# VFD-Clock.net
KiCad netlist of a schematic drawn in Altium Designer
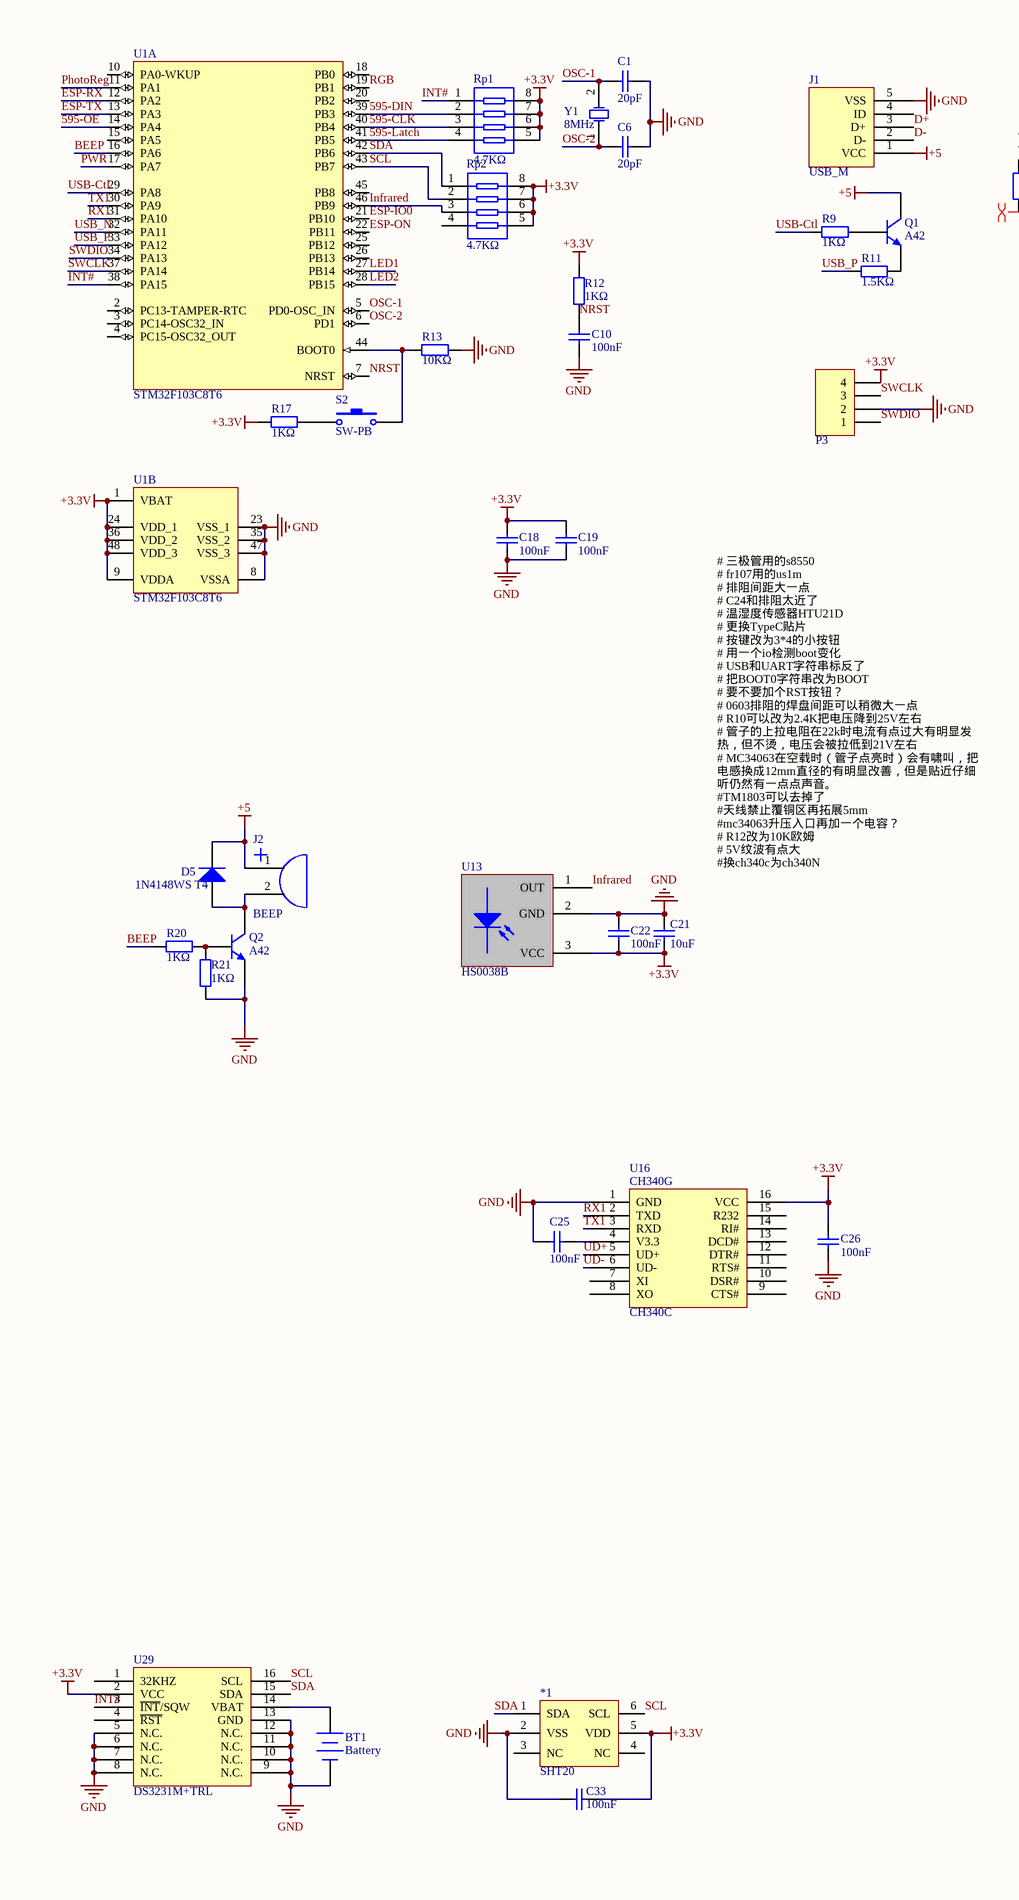
[diagram p0: VFD-Clock.SchDoc, left]
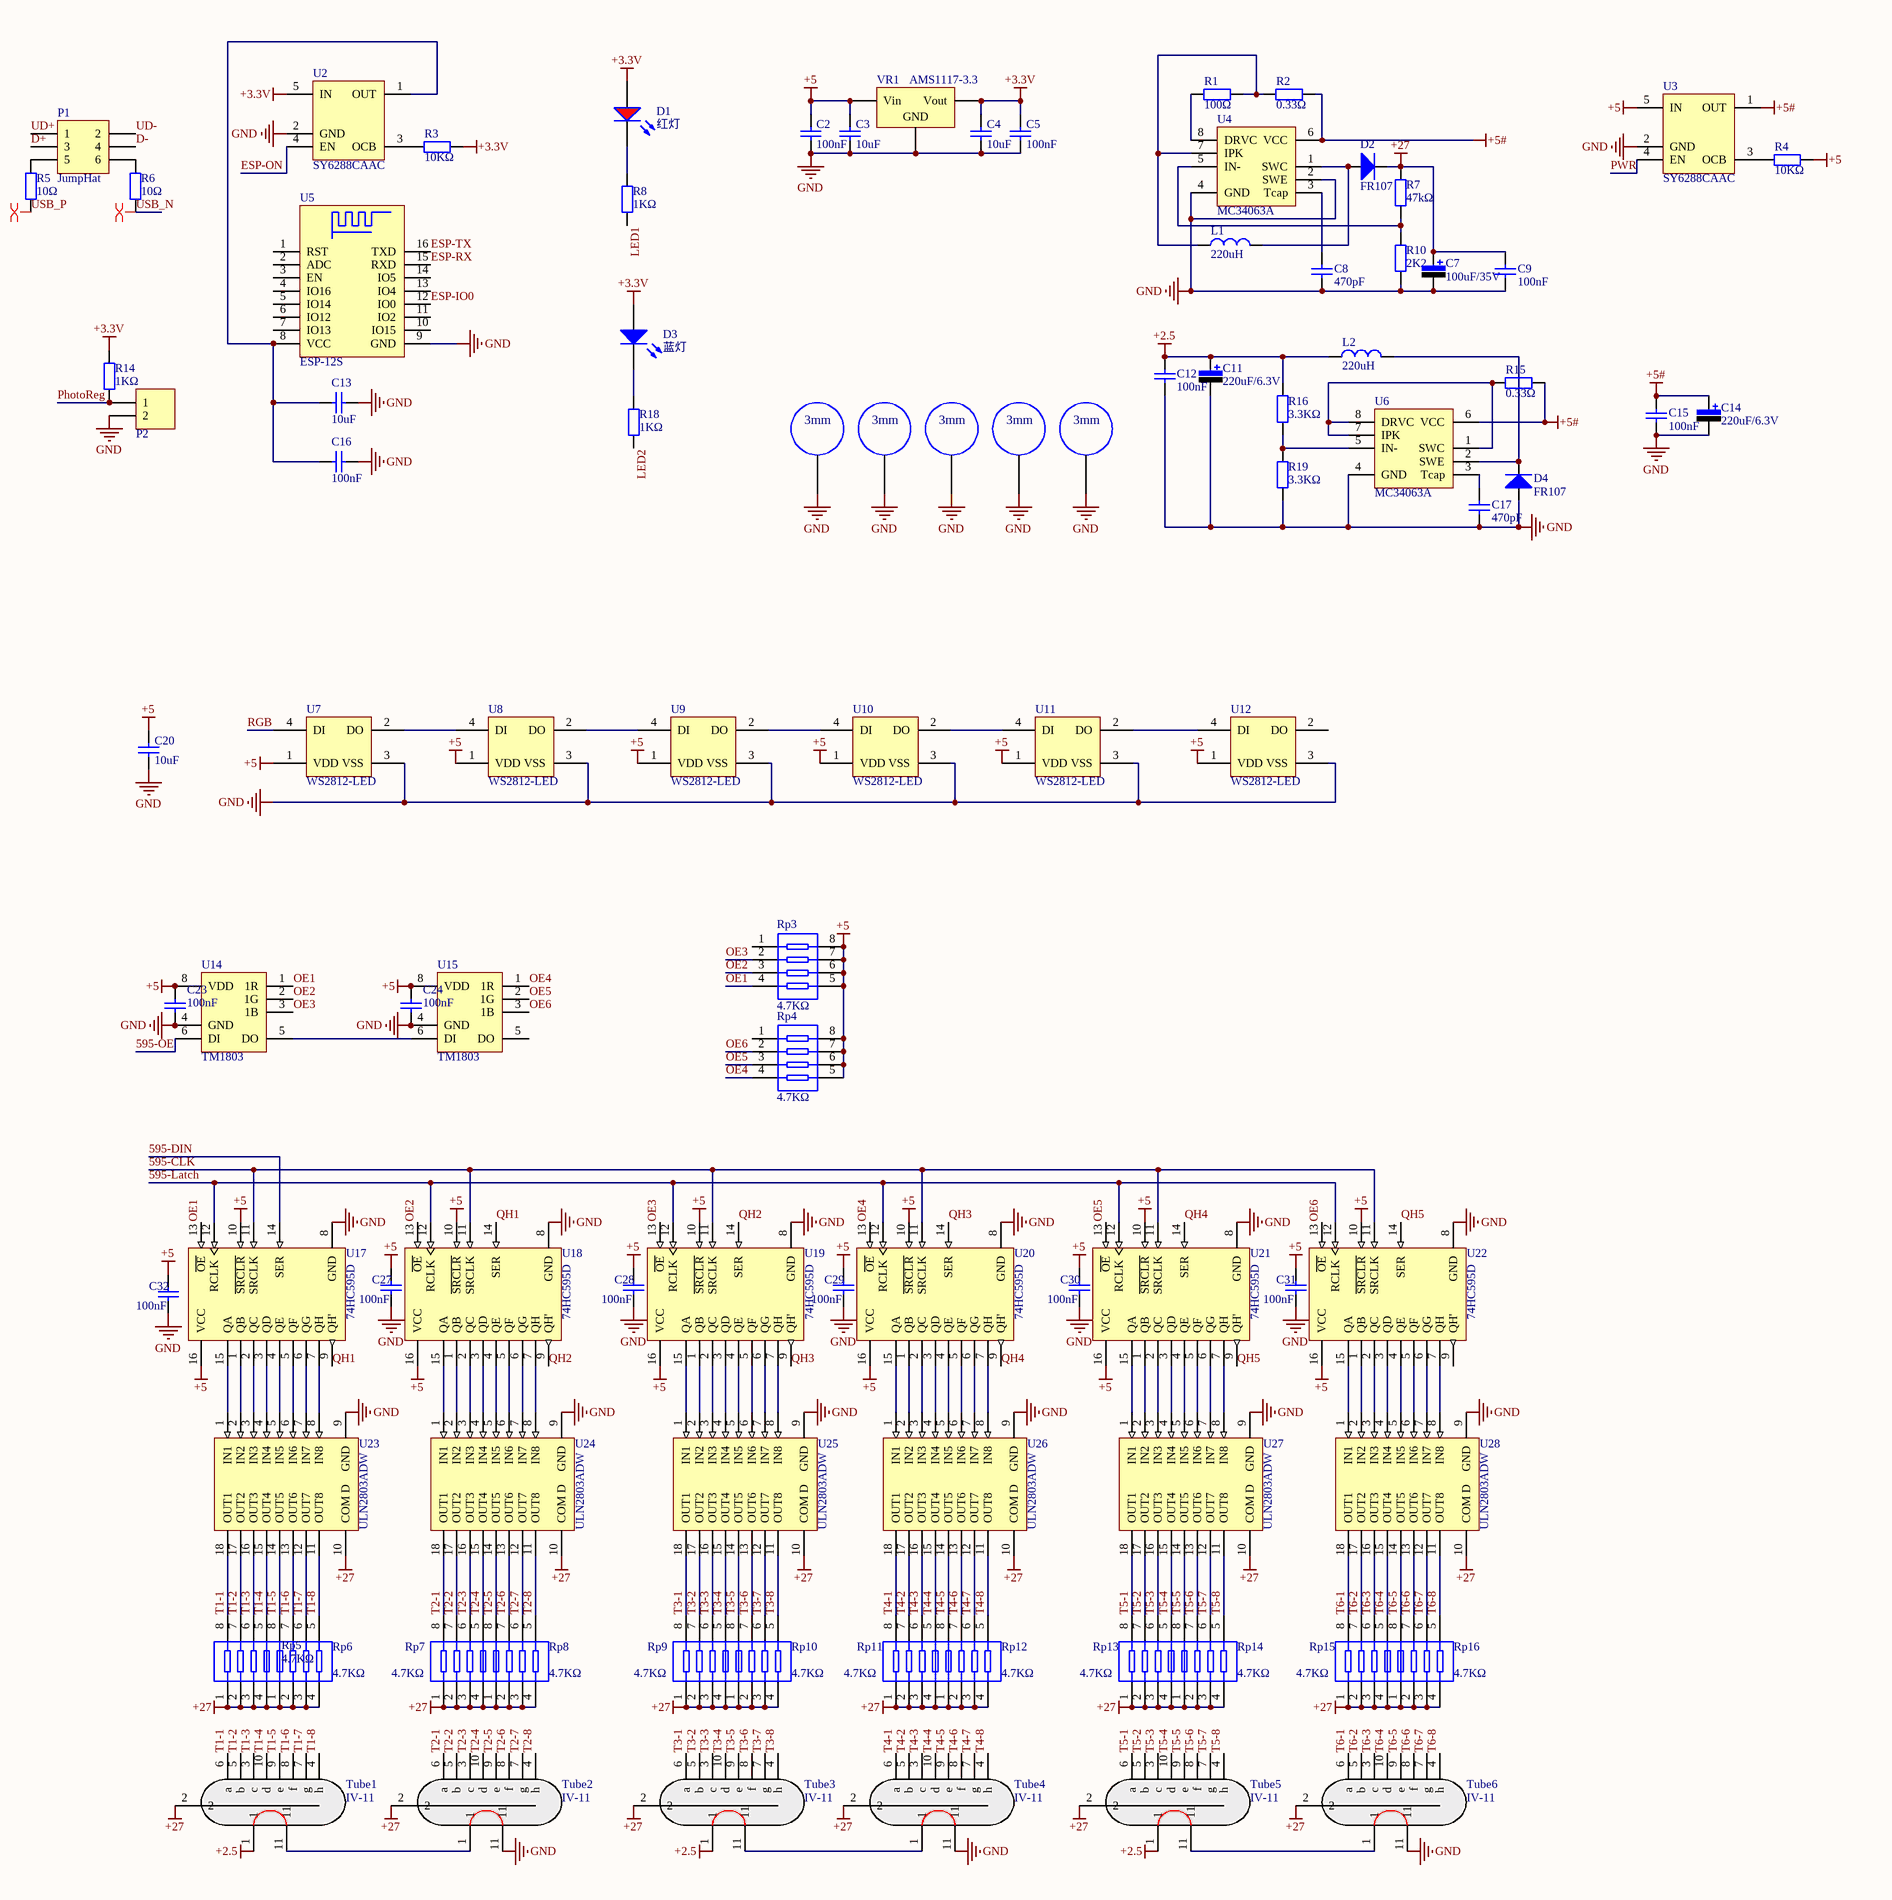
[diagram p1: VFD-Clock.SchDoc, right]

(export (version "E")
  (design (tool "Eeschema 10.0.6"))
  (components
    (comp (ref "*1")
      (value "SHT20")
      (footprint "DFN6")
      (description "温湿度传感器")
      (libsource (lib "fszhang") (part "SHT20"))
    )
    (comp (ref "BT1")
      (value "Battery")
      (footprint "CR1220")
      (description "备份电池")
      (fields (field (name "PUBLISHER") "Altium Limited"))
      (libsource (lib "fszhang") (part "Battery"))
    )
    (comp (ref "C1")
      (value "20pF")
      (footprint "0805_C")
      (description "贴片电容")
      (libsource (lib "Miscellaneous Devices LC") (part "0805 20pF (200) 5% 50V"))
    )
    (comp (ref "C2")
      (value "100nF")
      (footprint "0805_C")
      (description "贴片电容")
      (libsource (lib "Miscellaneous Devices LC") (part "0805 100nF(104) 10% 50V"))
    )
    (comp (ref "C3")
      (value "10uF")
      (footprint "0805_C")
      (description "贴片电容")
      (libsource (lib "Miscellaneous Devices LC") (part "0805 10uF (106) 10% 25V"))
    )
    (comp (ref "C4")
      (value "10uF")
      (footprint "0805_C")
      (description "贴片电容")
      (libsource (lib "Miscellaneous Devices LC") (part "0805 10uF (106) 10% 25V"))
    )
    (comp (ref "C5")
      (value "100nF")
      (footprint "0805_C")
      (description "贴片电容")
      (libsource (lib "Miscellaneous Devices LC") (part "0805 100nF(104) 10% 50V"))
    )
    (comp (ref "C6")
      (value "20pF")
      (footprint "0805_C")
      (description "贴片电容")
      (libsource (lib "Miscellaneous Devices LC") (part "0805 20pF (200) 5% 50V"))
    )
    (comp (ref "C7")
      (value "100uF/35V")
      (footprint "CAP-7343")
      (description "极性电解电容")
      (fields (field (name "PUBLISHER") "Altium Limited"))
      (libsource (lib "fszhang") (part "Cap Pol"))
    )
    (comp (ref "C8")
      (value "470pF")
      (footprint "0805_C")
      (description "贴片电容")
      (libsource (lib "Miscellaneous Devices LC") (part "0805 470pF (471) 10% 50V"))
    )
    (comp (ref "C9")
      (value "100nF")
      (footprint "0805_C")
      (description "贴片电容")
      (libsource (lib "Miscellaneous Devices LC") (part "0805 100nF(104) 10% 50V"))
    )
    (comp (ref "C10")
      (value "100nF")
      (footprint "0805_C")
      (description "贴片电容")
      (libsource (lib "Miscellaneous Devices LC") (part "0805 100nF(104) 10% 50V"))
    )
    (comp (ref "C11")
      (value "220uF/6.3V")
      (footprint "CAP-3528")
      (description "极性电解电容")
      (fields (field (name "PUBLISHER") "Altium Limited"))
      (libsource (lib "fszhang") (part "Cap Pol"))
    )
    (comp (ref "C12")
      (value "100nF")
      (footprint "0805_C")
      (description "贴片电容")
      (libsource (lib "Miscellaneous Devices LC") (part "0805 100nF(104) 10% 50V"))
    )
    (comp (ref "C13")
      (value "10uF")
      (footprint "0805_C")
      (description "贴片电容")
      (libsource (lib "Miscellaneous Devices LC") (part "0805 10uF (106) 10% 25V"))
    )
    (comp (ref "C14")
      (value "220uF/6.3V")
      (footprint "CAP-3528")
      (description "极性电解电容")
      (fields (field (name "PUBLISHER") "Altium Limited"))
      (libsource (lib "fszhang") (part "Cap Pol"))
    )
    (comp (ref "C15")
      (value "100nF")
      (footprint "0805_C")
      (description "贴片电容")
      (libsource (lib "Miscellaneous Devices LC") (part "0805 100nF(104) 10% 50V"))
    )
    (comp (ref "C16")
      (value "100nF")
      (footprint "0805_C")
      (description "贴片电容")
      (libsource (lib "Miscellaneous Devices LC") (part "0805 100nF(104) 10% 50V"))
    )
    (comp (ref "C17")
      (value "470pF")
      (footprint "0805_C")
      (description "贴片电容")
      (libsource (lib "Miscellaneous Devices LC") (part "0805 470pF (471) 10% 50V"))
    )
    (comp (ref "C18")
      (value "100nF")
      (footprint "0805_C")
      (description "贴片电容")
      (libsource (lib "Miscellaneous Devices LC") (part "0805 100nF(104) 10% 50V"))
    )
    (comp (ref "C19")
      (value "100nF")
      (footprint "0805_C")
      (description "贴片电容")
      (libsource (lib "Miscellaneous Devices LC") (part "0805 100nF(104) 10% 50V"))
    )
    (comp (ref "C20")
      (value "10uF")
      (footprint "0805_C")
      (description "贴片电容")
      (libsource (lib "Miscellaneous Devices LC") (part "0805 10uF (106) 10% 25V"))
    )
    (comp (ref "C21")
      (value "10uF")
      (footprint "0805_C")
      (description "贴片电容")
      (libsource (lib "Miscellaneous Devices LC") (part "0805 10uF (106) 10% 25V"))
    )
    (comp (ref "C22")
      (value "100nF")
      (footprint "0805_C")
      (description "贴片电容")
      (libsource (lib "Miscellaneous Devices LC") (part "0805 100nF(104) 10% 50V"))
    )
    (comp (ref "C23")
      (value "100nF")
      (footprint "0805_C")
      (description "贴片电容")
      (libsource (lib "Miscellaneous Devices LC") (part "0805 100nF(104) 10% 50V"))
    )
    (comp (ref "C24")
      (value "100nF")
      (footprint "0805_C")
      (description "贴片电容")
      (libsource (lib "Miscellaneous Devices LC") (part "0805 100nF(104) 10% 50V"))
    )
    (comp (ref "C25")
      (value "100nF")
      (footprint "0805_C")
      (description "贴片电容")
      (libsource (lib "Miscellaneous Devices LC") (part "0805 100nF(104) 10% 50V"))
    )
    (comp (ref "C26")
      (value "100nF")
      (footprint "0805_C")
      (description "贴片电容")
      (libsource (lib "Miscellaneous Devices LC") (part "0805 100nF(104) 10% 50V"))
    )
    (comp (ref "C27")
      (value "100nF")
      (footprint "0805_C")
      (description "贴片电容")
      (libsource (lib "Miscellaneous Devices LC") (part "0805 100nF(104) 10% 50V"))
    )
    (comp (ref "C28")
      (value "100nF")
      (footprint "0805_C")
      (description "贴片电容")
      (libsource (lib "Miscellaneous Devices LC") (part "0805 100nF(104) 10% 50V"))
    )
    (comp (ref "C29")
      (value "100nF")
      (footprint "0805_C")
      (description "贴片电容")
      (libsource (lib "Miscellaneous Devices LC") (part "0805 100nF(104) 10% 50V"))
    )
    (comp (ref "C30")
      (value "100nF")
      (footprint "0805_C")
      (description "贴片电容")
      (libsource (lib "Miscellaneous Devices LC") (part "0805 100nF(104) 10% 50V"))
    )
    (comp (ref "C31")
      (value "100nF")
      (footprint "0805_C")
      (description "贴片电容")
      (libsource (lib "Miscellaneous Devices LC") (part "0805 100nF(104) 10% 50V"))
    )
    (comp (ref "C32")
      (value "100nF")
      (footprint "0805_C")
      (description "贴片电容")
      (libsource (lib "Miscellaneous Devices LC") (part "0805 100nF(104) 10% 50V"))
    )
    (comp (ref "C33")
      (value "100nF")
      (footprint "0805_C")
      (description "贴片电容")
      (libsource (lib "Miscellaneous Devices LC") (part "0805 100nF(104) 10% 50V"))
    )
    (comp (ref "D1")
      (value "红灯")
      (footprint "0805_LED_S1")
      (description "发光二极管")
      (libsource (lib "Miscellaneous Devices LC") (part "0805 红灯"))
    )
    (comp (ref "D2")
      (value "FR107")
      (footprint "DIODE-SMA")
      (description "二极管")
      (fields (field (name "PUBLISHER") "Altium Limited"))
      (libsource (lib "fszhang") (part "Diode"))
    )
    (comp (ref "D3")
      (value "蓝灯")
      (footprint "0805_LED_S1")
      (description "发光二极管")
      (libsource (lib "Miscellaneous Devices LC") (part "0805 蓝灯"))
    )
    (comp (ref "D4")
      (value "FR107")
      (footprint "DIODE-SMA")
      (description "二极管")
      (fields (field (name "PUBLISHER") "Altium Limited"))
      (libsource (lib "fszhang") (part "Diode"))
    )
    (comp (ref "D5")
      (value "1N4148WS T4")
      (footprint "SOD-323")
      (description "二极管")
      (libsource (lib "Miscellaneous Devices LC") (part "SOD-323 1N4148WS T4"))
    )
    (comp (ref "J1")
      (value "USB_M")
      (footprint "USB_Micro2")
      (description "MicroUSB接口")
      (libsource (lib "fszhang") (part "USB_M"))
    )
    (comp (ref "J2")
      (value "BEEP")
      (footprint "BEEP-SMD-8530-3V-2.7KHZ")
      (description "蜂鸣器")
      (libsource (lib "fszhang") (part "BEEP"))
    )
    (comp (ref "L1")
      (value "220uH")
      (footprint "CDRH104R")
      (description "电感")
      (fields (field (name "PUBLISHER") "Altium Limited"))
      (libsource (lib "fszhang") (part "Inductor"))
    )
    (comp (ref "L2")
      (value "220uH")
      (footprint "CDRH104R")
      (description "电感")
      (fields (field (name "PUBLISHER") "Altium Limited"))
      (libsource (lib "fszhang") (part "Inductor"))
    )
    (comp (ref "P1")
      (value "JumpHat")
      (footprint "HDR2X3")
      (description "Header, 3-Pin, Dual row")
      (fields (field (name "PUBLISHER") "Altium Limited"))
      (libsource (lib "Miscellaneous Connectors") (part "Header 3X2"))
    )
    (comp (ref "P2")
      (value "Light Resister")
      (footprint "HDR2X1_A")
      (description "光敏电阻")
      (fields (field (name "PUBLISHER") "Altium Limited"))
      (libsource (lib "fszhang") (part "Header 2"))
    )
    (comp (ref "P3")
      (value "Header 4")
      (footprint "HDR4X1_A")
      (description "接插件")
      (fields (field (name "PUBLISHER") "Altium Limited"))
      (libsource (lib "fszhang") (part "Header 4"))
    )
    (comp (ref "Q1")
      (value "A42")
      (footprint "Miscellaneous Devices LC:SOT-23(SOT-23-3)")
      (description "三极管")
      (libsource (lib "Miscellaneous Devices LC") (part "SOT-23 SS8050 Y1"))
    )
    (comp (ref "Q2")
      (value "A42")
      (footprint "Miscellaneous Devices LC:SOT-23(SOT-23-3)")
      (description "三极管")
      (libsource (lib "Miscellaneous Devices LC") (part "SOT-23 SS8050 Y1"))
    )
    (comp (ref "R1")
      (value "100Ω")
      (footprint "0805_R")
      (description "贴片电阻")
      (libsource (lib "Miscellaneous Devices LC") (part "0805 100Ω (1000) 1%"))
    )
    (comp (ref "R2")
      (value "0.33Ω")
      (footprint "0805_R")
      (description "贴片电阻")
      (libsource (lib "Miscellaneous Devices LC") (part "0805 100Ω (1000) 1%"))
    )
    (comp (ref "R3")
      (value "10KΩ")
      (footprint "0805_R")
      (description "贴片电阻")
      (libsource (lib "Miscellaneous Devices LC") (part "0805 10KΩ (1002) 1%"))
    )
    (comp (ref "R4")
      (value "10KΩ")
      (footprint "0805_R")
      (description "贴片电阻")
      (libsource (lib "Miscellaneous Devices LC") (part "0805 10KΩ (1002) 1%"))
    )
    (comp (ref "R5")
      (value "10Ω")
      (footprint "0805_R")
      (description "贴片电阻")
      (libsource (lib "Miscellaneous Devices LC") (part "0805 10Ω (10R0) 1%"))
    )
    (comp (ref "R6")
      (value "10Ω")
      (footprint "0805_R")
      (description "贴片电阻")
      (libsource (lib "") (part "0805 10Ω (10R0) 1%_1"))
    )
    (comp (ref "R7")
      (value "47kΩ")
      (footprint "0805_R")
      (description "贴片电阻")
      (libsource (lib "") (part "0805 100Ω (1000) 1%_1"))
    )
    (comp (ref "R8")
      (value "1KΩ")
      (footprint "0805_R")
      (description "贴片电阻")
      (libsource (lib "") (part "0805 1KΩ (1001) 1%_3"))
    )
    (comp (ref "R9")
      (value "1KΩ")
      (footprint "0805_R")
      (description "贴片电阻")
      (libsource (lib "") (part "0805 1KΩ (1001) 1%_1"))
    )
    (comp (ref "R10")
      (value "2K2")
      (footprint "0805_R")
      (description "贴片电阻")
      (libsource (lib "") (part "0805 100Ω (1000) 1%_1"))
    )
    (comp (ref "R11")
      (value "1.5KΩ")
      (footprint "0805_R")
      (description "贴片电阻")
      (libsource (lib "Miscellaneous Devices LC") (part "0805 1.5KΩ (1501) 1%"))
    )
    (comp (ref "R12")
      (value "1KΩ")
      (footprint "0805_R")
      (description "贴片电阻")
      (libsource (lib "Miscellaneous Devices LC") (part "0805 1KΩ (1001) 1%"))
    )
    (comp (ref "R13")
      (value "10KΩ")
      (footprint "0805_R")
      (description "贴片电阻")
      (libsource (lib "") (part "0805 10KΩ (1002) 1%_1"))
    )
    (comp (ref "R14")
      (value "1KΩ")
      (footprint "0805_R")
      (description "贴片电阻")
      (libsource (lib "Miscellaneous Devices LC") (part "0805 1KΩ (1001) 1%"))
    )
    (comp (ref "R15")
      (value "0.33Ω")
      (footprint "0805_R")
      (description "贴片电阻")
      (libsource (lib "Miscellaneous Devices LC") (part "0805 100Ω (1000) 1%"))
    )
    (comp (ref "R16")
      (value "3.3KΩ")
      (footprint "0805_R")
      (description "贴片电阻")
      (libsource (lib "Miscellaneous Devices LC") (part "0805 3.3KΩ (3301) 1%"))
    )
    (comp (ref "R17")
      (value "1KΩ")
      (footprint "0805_R")
      (description "贴片电阻")
      (libsource (lib "") (part "0805 1KΩ (1001) 1%_2"))
    )
    (comp (ref "R18")
      (value "1KΩ")
      (footprint "0805_R")
      (description "贴片电阻")
      (libsource (lib "") (part "0805 1KΩ (1001) 1%_3"))
    )
    (comp (ref "R19")
      (value "3.3KΩ")
      (footprint "0805_R")
      (description "贴片电阻")
      (libsource (lib "Miscellaneous Devices LC") (part "0805 3.3KΩ (3301) 1%"))
    )
    (comp (ref "R20")
      (value "1KΩ")
      (footprint "0805_R")
      (description "贴片电阻")
      (libsource (lib "") (part "0805 1KΩ (1001) 1%_1"))
    )
    (comp (ref "R21")
      (value "1KΩ")
      (footprint "0805_R")
      (description "贴片电阻")
      (libsource (lib "Miscellaneous Devices LC") (part "0805 1KΩ (1001) 1%"))
    )
    (comp (ref "Rp1")
      (value "4.7KΩ")
      (footprint "0603_Rx4")
      (description "贴片排阻")
      (libsource (lib "Miscellaneous Devices LC") (part "0603*4  4.7KΩ (472) 5%"))
    )
    (comp (ref "Rp2")
      (value "4.7KΩ")
      (footprint "0603_Rx4")
      (description "贴片排阻")
      (libsource (lib "Miscellaneous Devices LC") (part "0603*4  4.7KΩ (472) 5%"))
    )
    (comp (ref "Rp3")
      (value "4.7KΩ")
      (footprint "0603_Rx4")
      (description "贴片排阻")
      (libsource (lib "Miscellaneous Devices LC") (part "0603*4  4.7KΩ (472) 5%"))
    )
    (comp (ref "Rp4")
      (value "4.7KΩ")
      (footprint "0603_Rx4")
      (description "贴片排阻")
      (libsource (lib "Miscellaneous Devices LC") (part "0603*4  4.7KΩ (472) 5%"))
    )
    (comp (ref "Rp5")
      (value "4.7KΩ")
      (footprint "0603_Rx4")
      (description "贴片排阻")
      (libsource (lib "Miscellaneous Devices LC") (part "0603*4  4.7KΩ (472) 5%"))
    )
    (comp (ref "Rp6")
      (value "4.7KΩ")
      (footprint "0603_Rx4")
      (description "贴片排阻")
      (libsource (lib "Miscellaneous Devices LC") (part "0603*4  4.7KΩ (472) 5%"))
    )
    (comp (ref "Rp7")
      (value "4.7KΩ")
      (footprint "0603_Rx4")
      (description "贴片排阻")
      (libsource (lib "Miscellaneous Devices LC") (part "0603*4  4.7KΩ (472) 5%"))
    )
    (comp (ref "Rp8")
      (value "4.7KΩ")
      (footprint "0603_Rx4")
      (description "贴片排阻")
      (libsource (lib "Miscellaneous Devices LC") (part "0603*4  4.7KΩ (472) 5%"))
    )
    (comp (ref "Rp9")
      (value "4.7KΩ")
      (footprint "0603_Rx4")
      (description "贴片排阻")
      (libsource (lib "Miscellaneous Devices LC") (part "0603*4  4.7KΩ (472) 5%"))
    )
    (comp (ref "Rp10")
      (value "4.7KΩ")
      (footprint "0603_Rx4")
      (description "贴片排阻")
      (libsource (lib "Miscellaneous Devices LC") (part "0603*4  4.7KΩ (472) 5%"))
    )
    (comp (ref "Rp11")
      (value "4.7KΩ")
      (footprint "0603_Rx4")
      (description "贴片排阻")
      (libsource (lib "Miscellaneous Devices LC") (part "0603*4  4.7KΩ (472) 5%"))
    )
    (comp (ref "Rp12")
      (value "4.7KΩ")
      (footprint "0603_Rx4")
      (description "贴片排阻")
      (libsource (lib "Miscellaneous Devices LC") (part "0603*4  4.7KΩ (472) 5%"))
    )
    (comp (ref "Rp13")
      (value "4.7KΩ")
      (footprint "0603_Rx4")
      (description "贴片排阻")
      (libsource (lib "Miscellaneous Devices LC") (part "0603*4  4.7KΩ (472) 5%"))
    )
    (comp (ref "Rp14")
      (value "4.7KΩ")
      (footprint "0603_Rx4")
      (description "贴片排阻")
      (libsource (lib "Miscellaneous Devices LC") (part "0603*4  4.7KΩ (472) 5%"))
    )
    (comp (ref "Rp15")
      (value "4.7KΩ")
      (footprint "0603_Rx4")
      (description "贴片排阻")
      (libsource (lib "Miscellaneous Devices LC") (part "0603*4  4.7KΩ (472) 5%"))
    )
    (comp (ref "Rp16")
      (value "4.7KΩ")
      (footprint "0603_Rx4")
      (description "贴片排阻")
      (libsource (lib "Miscellaneous Devices LC") (part "0603*4  4.7KΩ (472) 5%"))
    )
    (comp (ref "S2")
      (value "SW-PB")
      (footprint "SW_PB2_A1")
      (description "微动开关")
      (fields (field (name "PUBLISHER") "Altium Limited"))
      (libsource (lib "fszhang") (part "SW-PB"))
    )
    (comp (ref "T1") (value "M3铜柱螺丝孔") (footprint "螺丝孔-3mm") (libsource (lib "fszhang") (part "M3铜柱螺丝孔")))
    (comp (ref "T2") (value "M3铜柱螺丝孔") (footprint "螺丝孔-3mm") (libsource (lib "fszhang") (part "M3铜柱螺丝孔")))
    (comp (ref "T3") (value "M3铜柱螺丝孔") (footprint "螺丝孔-3mm") (libsource (lib "fszhang") (part "M3铜柱螺丝孔")))
    (comp (ref "T4") (value "M3铜柱螺丝孔") (footprint "螺丝孔-3mm") (libsource (lib "fszhang") (part "M3铜柱螺丝孔")))
    (comp (ref "T5") (value "M3铜柱螺丝孔") (footprint "螺丝孔-3mm") (libsource (lib "fszhang") (part "M3铜柱螺丝孔")))
    (comp (ref "Tube1")
      (value "IV-11")
      (footprint "IV-11-1")
      (description "荧光数码管")
      (libsource (lib "fszhang") (part "IV-11"))
    )
    (comp (ref "Tube2")
      (value "IV-11")
      (footprint "IV-11-1")
      (description "荧光数码管")
      (libsource (lib "fszhang") (part "IV-11"))
    )
    (comp (ref "Tube3")
      (value "IV-11")
      (footprint "IV-11-1")
      (description "荧光数码管")
      (libsource (lib "fszhang") (part "IV-11"))
    )
    (comp (ref "Tube4")
      (value "IV-11")
      (footprint "IV-11-1")
      (description "荧光数码管")
      (libsource (lib "fszhang") (part "IV-11"))
    )
    (comp (ref "Tube5")
      (value "IV-11")
      (footprint "IV-11-1")
      (description "荧光数码管")
      (libsource (lib "fszhang") (part "IV-11"))
    )
    (comp (ref "Tube6")
      (value "IV-11")
      (footprint "IV-11-1")
      (description "荧光数码管")
      (libsource (lib "fszhang") (part "IV-11"))
    )
    (comp (ref "U1")
      (value "STM32F103C8T6")
      (footprint "LQFP-48_7x7x05P")
      (description "ARM")
      (libsource (lib "Miscellaneous Devices LC") (part "STM32F103C8T6"))
    )
    (comp (ref "U2")
      (value "SY6288CAAC")
      (footprint "SOT-23-5")
      (description "5V2A功率开关芯片")
      (libsource (lib "fszhang") (part "SY6288CAAC"))
    )
    (comp (ref "U3")
      (value "SY6288CAAC")
      (footprint "SOT-23-5")
      (description "5V2A功率开关芯片")
      (libsource (lib "fszhang") (part "SY6288CAAC"))
    )
    (comp (ref "U4") (value "MC34063A") (footprint "SOP-8") (libsource (lib "fszhang") (part "MC34063A")))
    (comp (ref "U5")
      (value "ESP-12S")
      (footprint "ESP-12S/SMD-16")
      (description "ESP8266 串口WIFI 16Pin")
      (libsource (lib "fszhang") (part "ESP-12S"))
    )
    (comp (ref "U6") (value "MC34063A") (footprint "SOP-8") (libsource (lib "fszhang") (part "MC34063A")))
    (comp (ref "U7")
      (value "WS2812-LED")
      (footprint "WS2812")
      (libsource (lib "fszhang") (part "WS2812-LED"))
    )
    (comp (ref "U8")
      (value "WS2812-LED")
      (footprint "WS2812")
      (libsource (lib "fszhang") (part "WS2812-LED"))
    )
    (comp (ref "U9")
      (value "WS2812-LED")
      (footprint "WS2812")
      (libsource (lib "fszhang") (part "WS2812-LED"))
    )
    (comp (ref "U10")
      (value "WS2812-LED")
      (footprint "WS2812")
      (libsource (lib "fszhang") (part "WS2812-LED"))
    )
    (comp (ref "U11")
      (value "WS2812-LED")
      (footprint "WS2812")
      (libsource (lib "fszhang") (part "WS2812-LED"))
    )
    (comp (ref "U12")
      (value "WS2812-LED")
      (footprint "WS2812")
      (libsource (lib "fszhang") (part "WS2812-LED"))
    )
    (comp (ref "U13")
      (value "HS0038B")
      (footprint "HS0038B")
      (description "红外接收器")
      (libsource (lib "fszhang") (part "HS0038B"))
    )
    (comp (ref "U14")
      (value "TM1803")
      (footprint "SOP-8")
      (description "3通道RGB全彩驱动芯片")
      (libsource (lib "fszhang") (part "TM1803"))
    )
    (comp (ref "U15")
      (value "TM1803")
      (footprint "SOP-8")
      (description "3通道RGB全彩驱动芯片")
      (libsource (lib "fszhang") (part "TM1803"))
    )
    (comp (ref "U16")
      (value "CH340C")
      (footprint "SOIC-16_150mil")
      (description "USB")
      (libsource (lib "Miscellaneous Devices LC") (part "CH340G_[C14267]"))
    )
    (comp (ref "U17")
      (value "74HC595D")
      (footprint "SOIC-16_150mil")
      (description "74系列逻辑芯片")
      (libsource (lib "Miscellaneous Devices LC") (part "74HC595D_[C5947]"))
    )
    (comp (ref "U18")
      (value "74HC595D")
      (footprint "SOIC-16_150mil")
      (description "74系列逻辑芯片")
      (libsource (lib "Miscellaneous Devices LC") (part "74HC595D_[C5947]"))
    )
    (comp (ref "U19")
      (value "74HC595D")
      (footprint "SOIC-16_150mil")
      (description "74系列逻辑芯片")
      (libsource (lib "Miscellaneous Devices LC") (part "74HC595D_[C5947]"))
    )
    (comp (ref "U20")
      (value "74HC595D")
      (footprint "SOIC-16_150mil")
      (description "74系列逻辑芯片")
      (libsource (lib "Miscellaneous Devices LC") (part "74HC595D_[C5947]"))
    )
    (comp (ref "U21")
      (value "74HC595D")
      (footprint "SOIC-16_150mil")
      (description "74系列逻辑芯片")
      (libsource (lib "Miscellaneous Devices LC") (part "74HC595D_[C5947]"))
    )
    (comp (ref "U22")
      (value "74HC595D")
      (footprint "SOIC-16_150mil")
      (description "74系列逻辑芯片")
      (libsource (lib "Miscellaneous Devices LC") (part "74HC595D_[C5947]"))
    )
    (comp (ref "U23")
      (value "ULN2803ADW")
      (footprint "SOIC-18_300mil")
      (description "大电流驱动")
      (libsource (lib "Miscellaneous Devices LC") (part "ULN2803ADW_[C9683]"))
    )
    (comp (ref "U24")
      (value "ULN2803ADW")
      (footprint "SOIC-18_300mil")
      (description "大电流驱动")
      (libsource (lib "Miscellaneous Devices LC") (part "ULN2803ADW_[C9683]"))
    )
    (comp (ref "U25")
      (value "ULN2803ADW")
      (footprint "SOIC-18_300mil")
      (description "大电流驱动")
      (libsource (lib "Miscellaneous Devices LC") (part "ULN2803ADW_[C9683]"))
    )
    (comp (ref "U26")
      (value "ULN2803ADW")
      (footprint "SOIC-18_300mil")
      (description "大电流驱动")
      (libsource (lib "Miscellaneous Devices LC") (part "ULN2803ADW_[C9683]"))
    )
    (comp (ref "U27")
      (value "ULN2803ADW")
      (footprint "SOIC-18_300mil")
      (description "大电流驱动")
      (libsource (lib "Miscellaneous Devices LC") (part "ULN2803ADW_[C9683]"))
    )
    (comp (ref "U28")
      (value "ULN2803ADW")
      (footprint "SOIC-18_300mil")
      (description "大电流驱动")
      (libsource (lib "Miscellaneous Devices LC") (part "ULN2803ADW_[C9683]"))
    )
    (comp (ref "U29")
      (value "DS3231M+TRL")
      (footprint "SOIC-16_300mil")
      (description "实时时钟")
      (libsource (lib "Miscellaneous Devices LC") (part "DS3231M+TRL_[C37663]"))
    )
    (comp (ref "VR1")
      (value "AMS1117-3.3")
      (footprint "SOT-223")
      (description "低压差线性稳压(LDO)")
      (libsource (lib "Miscellaneous Devices LC") (part "SOT-223 AMS1117-3.3"))
    )
    (comp (ref "Y1")
      (value "8MHz")
      (footprint "SMD-5032_2P")
      (description "贴片晶振")
      (libsource (lib "Miscellaneous Devices LC") (part "SMD-5032_2P 8MHz 20ppm 20pF"))
    )
  )
  (nets
    (net (code "1") (name "+2.5") (class "Default")
      (node (ref "C11") (pin "1") (pinfunction "1_1") (pintype "passive"))
      (node (ref "C12") (pin "1") (pinfunction "1_1") (pintype "passive"))
      (node (ref "L2") (pin "1") (pinfunction "1_1") (pintype "passive"))
      (node (ref "R16") (pin "2") (pinfunction "2_2") (pintype "passive"))
      (node (ref "Tube1") (pin "1") (pinfunction "1_1") (pintype "passive"))
      (node (ref "Tube3") (pin "1") (pinfunction "1_1") (pintype "passive"))
      (node (ref "Tube5") (pin "1") (pinfunction "1_1") (pintype "passive"))
    )
    (net (code "2") (name "+3.3V") (class "Default")
      (node (ref "*1") (pin "5") (pinfunction "VDD_5") (pintype "passive"))
      (node (ref "C18") (pin "2") (pinfunction "2_2") (pintype "passive"))
      (node (ref "C19") (pin "2") (pinfunction "2_2") (pintype "passive"))
      (node (ref "C21") (pin "1") (pinfunction "1_1") (pintype "passive"))
      (node (ref "C22") (pin "1") (pinfunction "1_1") (pintype "passive"))
      (node (ref "C26") (pin "2") (pinfunction "2_2") (pintype "passive"))
      (node (ref "C33") (pin "2") (pinfunction "2_2") (pintype "passive"))
      (node (ref "C4") (pin "2") (pinfunction "2_2") (pintype "passive"))
      (node (ref "C5") (pin "2") (pinfunction "2_2") (pintype "passive"))
      (node (ref "D1") (pin "A") (pinfunction "A_A") (pintype "passive"))
      (node (ref "D3") (pin "A") (pinfunction "A_A") (pintype "passive"))
      (node (ref "P3") (pin "4") (pinfunction "4_4") (pintype "passive"))
      (node (ref "R12") (pin "2") (pinfunction "2_2") (pintype "passive"))
      (node (ref "R14") (pin "2") (pinfunction "2_2") (pintype "passive"))
      (node (ref "R17") (pin "2") (pinfunction "2_2") (pintype "passive"))
      (node (ref "R3") (pin "2") (pinfunction "2_2") (pintype "passive"))
      (node (ref "Rp1") (pin "5") (pinfunction "5_5") (pintype "passive"))
      (node (ref "Rp1") (pin "6") (pinfunction "6_6") (pintype "passive"))
      (node (ref "Rp1") (pin "7") (pinfunction "7_7") (pintype "passive"))
      (node (ref "Rp1") (pin "8") (pinfunction "8_8") (pintype "passive"))
      (node (ref "Rp2") (pin "5") (pinfunction "5_5") (pintype "passive"))
      (node (ref "Rp2") (pin "6") (pinfunction "6_6") (pintype "passive"))
      (node (ref "Rp2") (pin "7") (pinfunction "7_7") (pintype "passive"))
      (node (ref "Rp2") (pin "8") (pinfunction "8_8") (pintype "passive"))
      (node (ref "U1") (pin "1") (pinfunction "VBAT_1") (pintype "power_in"))
      (node (ref "U1") (pin "24") (pinfunction "VDD_1_24") (pintype "power_in"))
      (node (ref "U1") (pin "36") (pinfunction "VDD_2_36") (pintype "power_in"))
      (node (ref "U1") (pin "48") (pinfunction "VDD_3_48") (pintype "power_in"))
      (node (ref "U1") (pin "9") (pinfunction "VDDA_9") (pintype "power_in"))
      (node (ref "U13") (pin "3") (pinfunction "VCC_3") (pintype "passive"))
      (node (ref "U16") (pin "16") (pinfunction "VCC_16") (pintype "passive"))
      (node (ref "U2") (pin "5") (pinfunction "IN_5") (pintype "passive"))
      (node (ref "U29") (pin "2") (pinfunction "VCC_2") (pintype "passive"))
      (node (ref "VR1") (pin "2") (pinfunction "Vout_2") (pintype "passive"))
    )
    (net (code "3") (name "+5") (class "Default")
      (node (ref "C2") (pin "2") (pinfunction "2_2") (pintype "passive"))
      (node (ref "C20") (pin "2") (pinfunction "2_2") (pintype "passive"))
      (node (ref "C23") (pin "2") (pinfunction "2_2") (pintype "passive"))
      (node (ref "C24") (pin "2") (pinfunction "2_2") (pintype "passive"))
      (node (ref "C27") (pin "1") (pinfunction "1_1") (pintype "passive"))
      (node (ref "C28") (pin "1") (pinfunction "1_1") (pintype "passive"))
      (node (ref "C29") (pin "1") (pinfunction "1_1") (pintype "passive"))
      (node (ref "C3") (pin "2") (pinfunction "2_2") (pintype "passive"))
      (node (ref "C30") (pin "1") (pinfunction "1_1") (pintype "passive"))
      (node (ref "C31") (pin "1") (pinfunction "1_1") (pintype "passive"))
      (node (ref "C32") (pin "1") (pinfunction "1_1") (pintype "passive"))
      (node (ref "D5") (pin "2") (pinfunction "K_2") (pintype "passive"))
      (node (ref "J1") (pin "1") (pinfunction "VCC_1") (pintype "passive"))
      (node (ref "J2") (pin "1") (pinfunction "0_1") (pintype "passive"))
      (node (ref "Q1") (pin "3") (pinfunction "C_3") (pintype "passive"))
      (node (ref "R4") (pin "2") (pinfunction "2_2") (pintype "passive"))
      (node (ref "Rp3") (pin "5") (pinfunction "5_5") (pintype "passive"))
      (node (ref "Rp3") (pin "6") (pinfunction "6_6") (pintype "passive"))
      (node (ref "Rp3") (pin "7") (pinfunction "7_7") (pintype "passive"))
      (node (ref "Rp3") (pin "8") (pinfunction "8_8") (pintype "passive"))
      (node (ref "Rp4") (pin "5") (pinfunction "5_5") (pintype "passive"))
      (node (ref "Rp4") (pin "6") (pinfunction "6_6") (pintype "passive"))
      (node (ref "Rp4") (pin "7") (pinfunction "7_7") (pintype "passive"))
      (node (ref "Rp4") (pin "8") (pinfunction "8_8") (pintype "passive"))
      (node (ref "U10") (pin "1") (pinfunction "VDD_1") (pintype "passive"))
      (node (ref "U11") (pin "1") (pinfunction "VDD_1") (pintype "passive"))
      (node (ref "U12") (pin "1") (pinfunction "VDD_1") (pintype "passive"))
      (node (ref "U14") (pin "8") (pinfunction "VDD_8") (pintype "passive"))
      (node (ref "U15") (pin "8") (pinfunction "VDD_8") (pintype "passive"))
      (node (ref "U17") (pin "10") (pinfunction "~{SRCLR}_10") (pintype "input"))
      (node (ref "U17") (pin "16") (pinfunction "VCC_16") (pintype "power_in"))
      (node (ref "U18") (pin "10") (pinfunction "~{SRCLR}_10") (pintype "input"))
      (node (ref "U18") (pin "16") (pinfunction "VCC_16") (pintype "power_in"))
      (node (ref "U19") (pin "10") (pinfunction "~{SRCLR}_10") (pintype "input"))
      (node (ref "U19") (pin "16") (pinfunction "VCC_16") (pintype "power_in"))
      (node (ref "U20") (pin "10") (pinfunction "~{SRCLR}_10") (pintype "input"))
      (node (ref "U20") (pin "16") (pinfunction "VCC_16") (pintype "power_in"))
      (node (ref "U21") (pin "10") (pinfunction "~{SRCLR}_10") (pintype "input"))
      (node (ref "U21") (pin "16") (pinfunction "VCC_16") (pintype "power_in"))
      (node (ref "U22") (pin "10") (pinfunction "~{SRCLR}_10") (pintype "input"))
      (node (ref "U22") (pin "16") (pinfunction "VCC_16") (pintype "power_in"))
      (node (ref "U3") (pin "5") (pinfunction "IN_5") (pintype "passive"))
      (node (ref "U7") (pin "1") (pinfunction "VDD_1") (pintype "passive"))
      (node (ref "U8") (pin "1") (pinfunction "VDD_1") (pintype "passive"))
      (node (ref "U9") (pin "1") (pinfunction "VDD_1") (pintype "passive"))
      (node (ref "VR1") (pin "3") (pinfunction "Vin_3") (pintype "passive"))
    )
    (net (code "4") (name "+5#") (class "Default")
      (node (ref "C14") (pin "1") (pinfunction "1_1") (pintype "passive"))
      (node (ref "C15") (pin "1") (pinfunction "1_1") (pintype "passive"))
      (node (ref "R15") (pin "2") (pinfunction "2_2") (pintype "passive"))
      (node (ref "R2") (pin "2") (pinfunction "2_2") (pintype "passive"))
      (node (ref "U3") (pin "1") (pinfunction "OUT_1") (pintype "passive"))
      (node (ref "U4") (pin "6") (pinfunction "VCC_6") (pintype "passive"))
      (node (ref "U6") (pin "6") (pinfunction "VCC_6") (pintype "passive"))
    )
    (net (code "5") (name "+27") (class "Default")
      (node (ref "C7") (pin "1") (pinfunction "1_1") (pintype "passive"))
      (node (ref "C9") (pin "1") (pinfunction "1_1") (pintype "passive"))
      (node (ref "D2") (pin "2") (pinfunction "K_2") (pintype "passive"))
      (node (ref "R7") (pin "2") (pinfunction "2_2") (pintype "passive"))
      (node (ref "Rp10") (pin "1") (pinfunction "1_1") (pintype "passive"))
      (node (ref "Rp10") (pin "2") (pinfunction "2_2") (pintype "passive"))
      (node (ref "Rp10") (pin "3") (pinfunction "3_3") (pintype "passive"))
      (node (ref "Rp10") (pin "4") (pinfunction "4_4") (pintype "passive"))
      (node (ref "Rp11") (pin "1") (pinfunction "1_1") (pintype "passive"))
      (node (ref "Rp11") (pin "2") (pinfunction "2_2") (pintype "passive"))
      (node (ref "Rp11") (pin "3") (pinfunction "3_3") (pintype "passive"))
      (node (ref "Rp11") (pin "4") (pinfunction "4_4") (pintype "passive"))
      (node (ref "Rp12") (pin "1") (pinfunction "1_1") (pintype "passive"))
      (node (ref "Rp12") (pin "2") (pinfunction "2_2") (pintype "passive"))
      (node (ref "Rp12") (pin "3") (pinfunction "3_3") (pintype "passive"))
      (node (ref "Rp12") (pin "4") (pinfunction "4_4") (pintype "passive"))
      (node (ref "Rp13") (pin "1") (pinfunction "1_1") (pintype "passive"))
      (node (ref "Rp13") (pin "2") (pinfunction "2_2") (pintype "passive"))
      (node (ref "Rp13") (pin "3") (pinfunction "3_3") (pintype "passive"))
      (node (ref "Rp13") (pin "4") (pinfunction "4_4") (pintype "passive"))
      (node (ref "Rp14") (pin "1") (pinfunction "1_1") (pintype "passive"))
      (node (ref "Rp14") (pin "2") (pinfunction "2_2") (pintype "passive"))
      (node (ref "Rp14") (pin "3") (pinfunction "3_3") (pintype "passive"))
      (node (ref "Rp14") (pin "4") (pinfunction "4_4") (pintype "passive"))
      (node (ref "Rp15") (pin "1") (pinfunction "1_1") (pintype "passive"))
      (node (ref "Rp15") (pin "2") (pinfunction "2_2") (pintype "passive"))
      (node (ref "Rp15") (pin "3") (pinfunction "3_3") (pintype "passive"))
      (node (ref "Rp15") (pin "4") (pinfunction "4_4") (pintype "passive"))
      (node (ref "Rp16") (pin "1") (pinfunction "1_1") (pintype "passive"))
      (node (ref "Rp16") (pin "2") (pinfunction "2_2") (pintype "passive"))
      (node (ref "Rp16") (pin "3") (pinfunction "3_3") (pintype "passive"))
      (node (ref "Rp16") (pin "4") (pinfunction "4_4") (pintype "passive"))
      (node (ref "Rp5") (pin "1") (pinfunction "1_1") (pintype "passive"))
      (node (ref "Rp5") (pin "2") (pinfunction "2_2") (pintype "passive"))
      (node (ref "Rp5") (pin "3") (pinfunction "3_3") (pintype "passive"))
      (node (ref "Rp5") (pin "4") (pinfunction "4_4") (pintype "passive"))
      (node (ref "Rp6") (pin "1") (pinfunction "1_1") (pintype "passive"))
      (node (ref "Rp6") (pin "2") (pinfunction "2_2") (pintype "passive"))
      (node (ref "Rp6") (pin "3") (pinfunction "3_3") (pintype "passive"))
      (node (ref "Rp6") (pin "4") (pinfunction "4_4") (pintype "passive"))
      (node (ref "Rp7") (pin "1") (pinfunction "1_1") (pintype "passive"))
      (node (ref "Rp7") (pin "2") (pinfunction "2_2") (pintype "passive"))
      (node (ref "Rp7") (pin "3") (pinfunction "3_3") (pintype "passive"))
      (node (ref "Rp7") (pin "4") (pinfunction "4_4") (pintype "passive"))
      (node (ref "Rp8") (pin "1") (pinfunction "1_1") (pintype "passive"))
      (node (ref "Rp8") (pin "2") (pinfunction "2_2") (pintype "passive"))
      (node (ref "Rp8") (pin "3") (pinfunction "3_3") (pintype "passive"))
      (node (ref "Rp8") (pin "4") (pinfunction "4_4") (pintype "passive"))
      (node (ref "Rp9") (pin "1") (pinfunction "1_1") (pintype "passive"))
      (node (ref "Rp9") (pin "2") (pinfunction "2_2") (pintype "passive"))
      (node (ref "Rp9") (pin "3") (pinfunction "3_3") (pintype "passive"))
      (node (ref "Rp9") (pin "4") (pinfunction "4_4") (pintype "passive"))
      (node (ref "Tube1") (pin "2") (pinfunction "2_2") (pintype "passive"))
      (node (ref "Tube2") (pin "2") (pinfunction "2_2") (pintype "passive"))
      (node (ref "Tube3") (pin "2") (pinfunction "2_2") (pintype "passive"))
      (node (ref "Tube4") (pin "2") (pinfunction "2_2") (pintype "passive"))
      (node (ref "Tube5") (pin "2") (pinfunction "2_2") (pintype "passive"))
      (node (ref "Tube6") (pin "2") (pinfunction "2_2") (pintype "passive"))
      (node (ref "U23") (pin "10") (pinfunction "COM_D_10") (pintype "passive"))
      (node (ref "U24") (pin "10") (pinfunction "COM_D_10") (pintype "passive"))
      (node (ref "U25") (pin "10") (pinfunction "COM_D_10") (pintype "passive"))
      (node (ref "U26") (pin "10") (pinfunction "COM_D_10") (pintype "passive"))
      (node (ref "U27") (pin "10") (pinfunction "COM_D_10") (pintype "passive"))
      (node (ref "U28") (pin "10") (pinfunction "COM_D_10") (pintype "passive"))
    )
    (net (code "6") (name "/595-CLK") (class "Default")
      (node (ref "Rp1") (pin "3") (pinfunction "3_3") (pintype "passive"))
      (node (ref "U1") (pin "40") (pinfunction "PB4_40") (pintype "bidirectional"))
      (node (ref "U17") (pin "11") (pinfunction "SRCLK_11") (pintype "input"))
      (node (ref "U18") (pin "11") (pinfunction "SRCLK_11") (pintype "input"))
      (node (ref "U19") (pin "11") (pinfunction "SRCLK_11") (pintype "input"))
      (node (ref "U20") (pin "11") (pinfunction "SRCLK_11") (pintype "input"))
      (node (ref "U21") (pin "11") (pinfunction "SRCLK_11") (pintype "input"))
      (node (ref "U22") (pin "11") (pinfunction "SRCLK_11") (pintype "input"))
    )
    (net (code "7") (name "/595-DIN") (class "Default")
      (node (ref "Rp1") (pin "2") (pinfunction "2_2") (pintype "passive"))
      (node (ref "U1") (pin "39") (pinfunction "PB3_39") (pintype "bidirectional"))
      (node (ref "U17") (pin "14") (pinfunction "SER_14") (pintype "input"))
    )
    (net (code "8") (name "/595-Latch") (class "Default")
      (node (ref "Rp1") (pin "4") (pinfunction "4_4") (pintype "passive"))
      (node (ref "U1") (pin "41") (pinfunction "PB5_41") (pintype "bidirectional"))
      (node (ref "U17") (pin "12") (pinfunction "RCLK_12") (pintype "input"))
      (node (ref "U18") (pin "12") (pinfunction "RCLK_12") (pintype "input"))
      (node (ref "U19") (pin "12") (pinfunction "RCLK_12") (pintype "input"))
      (node (ref "U20") (pin "12") (pinfunction "RCLK_12") (pintype "input"))
      (node (ref "U21") (pin "12") (pinfunction "RCLK_12") (pintype "input"))
      (node (ref "U22") (pin "12") (pinfunction "RCLK_12") (pintype "input"))
    )
    (net (code "9") (name "/595-OE") (class "Default")
      (node (ref "U1") (pin "14") (pinfunction "PA4_14") (pintype "bidirectional"))
      (node (ref "U14") (pin "6") (pinfunction "DI_6") (pintype "passive"))
    )
    (net (code "10") (name "/BEEP") (class "Default")
      (node (ref "R20") (pin "1") (pinfunction "1_1") (pintype "passive"))
      (node (ref "U1") (pin "16") (pinfunction "PA6_16") (pintype "bidirectional"))
    )
    (net (code "11") (name "/D+") (class "Default")
      (node (ref "J1") (pin "3") (pinfunction "D+_3") (pintype "passive"))
      (node (ref "P1") (pin "3") (pinfunction "3_3") (pintype "passive"))
    )
    (net (code "12") (name "/D-") (class "Default")
      (node (ref "J1") (pin "2") (pinfunction "D-_2") (pintype "passive"))
      (node (ref "P1") (pin "4") (pinfunction "4_4") (pintype "passive"))
    )
    (net (code "13") (name "/ESP-IO0") (class "Default")
      (node (ref "U1") (pin "21") (pinfunction "PB10_21") (pintype "bidirectional"))
      (node (ref "U5") (pin "12") (pinfunction "IO0_12") (pintype "passive"))
    )
    (net (code "14") (name "/ESP-ON") (class "Default")
      (node (ref "U1") (pin "22") (pinfunction "PB11_22") (pintype "bidirectional"))
      (node (ref "U2") (pin "4") (pinfunction "EN_4") (pintype "passive"))
    )
    (net (code "15") (name "/ESP-RX") (class "Default")
      (node (ref "U1") (pin "12") (pinfunction "PA2_12") (pintype "bidirectional"))
      (node (ref "U5") (pin "15") (pinfunction "RXD_15") (pintype "passive"))
    )
    (net (code "16") (name "/ESP-TX") (class "Default")
      (node (ref "U1") (pin "13") (pinfunction "PA3_13") (pintype "bidirectional"))
      (node (ref "U5") (pin "16") (pinfunction "TXD_16") (pintype "passive"))
    )
    (net (code "17") (name "/INT#") (class "Default")
      (node (ref "Rp1") (pin "1") (pinfunction "1_1") (pintype "passive"))
      (node (ref "U1") (pin "38") (pinfunction "PA15_38") (pintype "bidirectional"))
      (node (ref "U29") (pin "3") (pinfunction "~{INT}/SQW_3") (pintype "passive"))
    )
    (net (code "18") (name "/Infrared") (class "Default")
      (node (ref "Rp2") (pin "3") (pinfunction "3_3") (pintype "passive"))
      (node (ref "U1") (pin "46") (pinfunction "PB9_46") (pintype "bidirectional"))
      (node (ref "U13") (pin "1") (pinfunction "OUT_1") (pintype "passive"))
    )
    (net (code "19") (name "/LED1") (class "Default")
      (node (ref "R8") (pin "2") (pinfunction "2_2") (pintype "passive"))
      (node (ref "U1") (pin "27") (pinfunction "PB14_27") (pintype "bidirectional"))
    )
    (net (code "20") (name "/LED2") (class "Default")
      (node (ref "R18") (pin "2") (pinfunction "2_2") (pintype "passive"))
      (node (ref "U1") (pin "28") (pinfunction "PB15_28") (pintype "bidirectional"))
    )
    (net (code "21") (name "/NRST") (class "Default")
      (node (ref "C10") (pin "2") (pinfunction "2_2") (pintype "passive"))
      (node (ref "R12") (pin "1") (pinfunction "1_1") (pintype "passive"))
      (node (ref "U1") (pin "7") (pinfunction "NRST_7") (pintype "bidirectional"))
    )
    (net (code "22") (name "/OE1") (class "Default")
      (node (ref "Rp3") (pin "4") (pinfunction "4_4") (pintype "passive"))
      (node (ref "U14") (pin "1") (pinfunction "1R_1") (pintype "passive"))
      (node (ref "U17") (pin "13") (pinfunction "~{OE}_13") (pintype "input"))
    )
    (net (code "23") (name "/OE2") (class "Default")
      (node (ref "Rp3") (pin "3") (pinfunction "3_3") (pintype "passive"))
      (node (ref "U14") (pin "2") (pinfunction "1G_2") (pintype "passive"))
      (node (ref "U18") (pin "13") (pinfunction "~{OE}_13") (pintype "input"))
    )
    (net (code "24") (name "/OE3") (class "Default")
      (node (ref "Rp3") (pin "2") (pinfunction "2_2") (pintype "passive"))
      (node (ref "U14") (pin "3") (pinfunction "1B_3") (pintype "passive"))
      (node (ref "U19") (pin "13") (pinfunction "~{OE}_13") (pintype "input"))
    )
    (net (code "25") (name "/OE4") (class "Default")
      (node (ref "Rp4") (pin "4") (pinfunction "4_4") (pintype "passive"))
      (node (ref "U15") (pin "1") (pinfunction "1R_1") (pintype "passive"))
      (node (ref "U20") (pin "13") (pinfunction "~{OE}_13") (pintype "input"))
    )
    (net (code "26") (name "/OE5") (class "Default")
      (node (ref "Rp4") (pin "3") (pinfunction "3_3") (pintype "passive"))
      (node (ref "U15") (pin "2") (pinfunction "1G_2") (pintype "passive"))
      (node (ref "U21") (pin "13") (pinfunction "~{OE}_13") (pintype "input"))
    )
    (net (code "27") (name "/OE6") (class "Default")
      (node (ref "Rp4") (pin "2") (pinfunction "2_2") (pintype "passive"))
      (node (ref "U15") (pin "3") (pinfunction "1B_3") (pintype "passive"))
      (node (ref "U22") (pin "13") (pinfunction "~{OE}_13") (pintype "input"))
    )
    (net (code "28") (name "/OSC-1") (class "Default")
      (node (ref "C1") (pin "1") (pinfunction "1_1") (pintype "passive"))
      (node (ref "U1") (pin "5") (pinfunction "PD0-OSC_IN_5") (pintype "bidirectional"))
      (node (ref "Y1") (pin "2") (pinfunction "OSC2_2") (pintype "passive"))
    )
    (net (code "29") (name "/OSC-2") (class "Default")
      (node (ref "C6") (pin "1") (pinfunction "1_1") (pintype "passive"))
      (node (ref "U1") (pin "6") (pinfunction "PD1_6") (pintype "bidirectional"))
      (node (ref "Y1") (pin "1") (pinfunction "OSC1_1") (pintype "passive"))
    )
    (net (code "30") (name "/PWR") (class "Default")
      (node (ref "U1") (pin "17") (pinfunction "PA7_17") (pintype "bidirectional"))
      (node (ref "U3") (pin "4") (pinfunction "EN_4") (pintype "passive"))
    )
    (net (code "31") (name "/PhotoReg") (class "Default")
      (node (ref "P2") (pin "1") (pinfunction "1_1") (pintype "passive"))
      (node (ref "R14") (pin "1") (pinfunction "1_1") (pintype "passive"))
      (node (ref "U1") (pin "11") (pinfunction "PA1_11") (pintype "bidirectional"))
    )
    (net (code "32") (name "/QH1") (class "Default")
      (node (ref "U17") (pin "9") (pinfunction "QH'_9") (pintype "output"))
      (node (ref "U18") (pin "14") (pinfunction "SER_14") (pintype "input"))
    )
    (net (code "33") (name "/QH2") (class "Default")
      (node (ref "U18") (pin "9") (pinfunction "QH'_9") (pintype "output"))
      (node (ref "U19") (pin "14") (pinfunction "SER_14") (pintype "input"))
    )
    (net (code "34") (name "/QH3") (class "Default")
      (node (ref "U19") (pin "9") (pinfunction "QH'_9") (pintype "output"))
      (node (ref "U20") (pin "14") (pinfunction "SER_14") (pintype "input"))
    )
    (net (code "35") (name "/QH4") (class "Default")
      (node (ref "U20") (pin "9") (pinfunction "QH'_9") (pintype "output"))
      (node (ref "U21") (pin "14") (pinfunction "SER_14") (pintype "input"))
    )
    (net (code "36") (name "/QH5") (class "Default")
      (node (ref "U21") (pin "9") (pinfunction "QH'_9") (pintype "output"))
      (node (ref "U22") (pin "14") (pinfunction "SER_14") (pintype "input"))
    )
    (net (code "37") (name "/RGB") (class "Default")
      (node (ref "U1") (pin "19") (pinfunction "PB1_19") (pintype "bidirectional"))
      (node (ref "U7") (pin "4") (pinfunction "DI_4") (pintype "passive"))
    )
    (net (code "38") (name "/RX1") (class "Default")
      (node (ref "U1") (pin "31") (pinfunction "PA10_31") (pintype "bidirectional"))
      (node (ref "U16") (pin "2") (pinfunction "TXD_2") (pintype "passive"))
    )
    (net (code "39") (name "/SCL") (class "Default")
      (node (ref "*1") (pin "6") (pinfunction "SCL_6") (pintype "passive"))
      (node (ref "Rp2") (pin "2") (pinfunction "2_2") (pintype "passive"))
      (node (ref "U1") (pin "43") (pinfunction "PB7_43") (pintype "bidirectional"))
      (node (ref "U29") (pin "16") (pinfunction "SCL_16") (pintype "passive"))
    )
    (net (code "40") (name "/SDA") (class "Default")
      (node (ref "*1") (pin "1") (pinfunction "SDA_1") (pintype "passive"))
      (node (ref "Rp2") (pin "1") (pinfunction "1_1") (pintype "passive"))
      (node (ref "U1") (pin "42") (pinfunction "PB6_42") (pintype "bidirectional"))
      (node (ref "U29") (pin "15") (pinfunction "SDA_15") (pintype "passive"))
    )
    (net (code "41") (name "/SWCLK") (class "Default")
      (node (ref "P3") (pin "3") (pinfunction "3_3") (pintype "passive"))
      (node (ref "U1") (pin "37") (pinfunction "PA14_37") (pintype "bidirectional"))
    )
    (net (code "42") (name "/SWDIO") (class "Default")
      (node (ref "P3") (pin "1") (pinfunction "1_1") (pintype "passive"))
      (node (ref "U1") (pin "34") (pinfunction "PA13_34") (pintype "bidirectional"))
    )
    (net (code "43") (name "/T1-1") (class "Default")
      (node (ref "Rp5") (pin "8") (pinfunction "8_8") (pintype "passive"))
      (node (ref "Tube1") (pin "6") (pinfunction "a_6") (pintype "passive"))
      (node (ref "U23") (pin "18") (pinfunction "OUT1_18") (pintype "open_collector"))
    )
    (net (code "44") (name "/T1-2") (class "Default")
      (node (ref "Rp5") (pin "7") (pinfunction "7_7") (pintype "passive"))
      (node (ref "Tube1") (pin "5") (pinfunction "b_5") (pintype "passive"))
      (node (ref "U23") (pin "17") (pinfunction "OUT2_17") (pintype "open_collector"))
    )
    (net (code "45") (name "/T1-3") (class "Default")
      (node (ref "Rp5") (pin "6") (pinfunction "6_6") (pintype "passive"))
      (node (ref "Tube1") (pin "3") (pinfunction "c_3") (pintype "passive"))
      (node (ref "U23") (pin "16") (pinfunction "OUT3_16") (pintype "open_collector"))
    )
    (net (code "46") (name "/T1-4") (class "Default")
      (node (ref "Rp5") (pin "5") (pinfunction "5_5") (pintype "passive"))
      (node (ref "Tube1") (pin "10") (pinfunction "d_10") (pintype "passive"))
      (node (ref "U23") (pin "15") (pinfunction "OUT4_15") (pintype "open_collector"))
    )
    (net (code "47") (name "/T1-5") (class "Default")
      (node (ref "Rp6") (pin "8") (pinfunction "8_8") (pintype "passive"))
      (node (ref "Tube1") (pin "9") (pinfunction "e_9") (pintype "passive"))
      (node (ref "U23") (pin "14") (pinfunction "OUT5_14") (pintype "open_collector"))
    )
    (net (code "48") (name "/T1-6") (class "Default")
      (node (ref "Rp6") (pin "7") (pinfunction "7_7") (pintype "passive"))
      (node (ref "Tube1") (pin "8") (pinfunction "f_8") (pintype "passive"))
      (node (ref "U23") (pin "13") (pinfunction "OUT6_13") (pintype "open_collector"))
    )
    (net (code "49") (name "/T1-7") (class "Default")
      (node (ref "Rp6") (pin "6") (pinfunction "6_6") (pintype "passive"))
      (node (ref "Tube1") (pin "7") (pinfunction "g_7") (pintype "passive"))
      (node (ref "U23") (pin "12") (pinfunction "OUT7_12") (pintype "open_collector"))
    )
    (net (code "50") (name "/T1-8") (class "Default")
      (node (ref "Rp6") (pin "5") (pinfunction "5_5") (pintype "passive"))
      (node (ref "Tube1") (pin "4") (pinfunction "h_4") (pintype "passive"))
      (node (ref "U23") (pin "11") (pinfunction "OUT8_11") (pintype "open_collector"))
    )
    (net (code "51") (name "/T2-1") (class "Default")
      (node (ref "Rp7") (pin "8") (pinfunction "8_8") (pintype "passive"))
      (node (ref "Tube2") (pin "6") (pinfunction "a_6") (pintype "passive"))
      (node (ref "U24") (pin "18") (pinfunction "OUT1_18") (pintype "open_collector"))
    )
    (net (code "52") (name "/T2-2") (class "Default")
      (node (ref "Rp7") (pin "7") (pinfunction "7_7") (pintype "passive"))
      (node (ref "Tube2") (pin "5") (pinfunction "b_5") (pintype "passive"))
      (node (ref "U24") (pin "17") (pinfunction "OUT2_17") (pintype "open_collector"))
    )
    (net (code "53") (name "/T2-3") (class "Default")
      (node (ref "Rp7") (pin "6") (pinfunction "6_6") (pintype "passive"))
      (node (ref "Tube2") (pin "3") (pinfunction "c_3") (pintype "passive"))
      (node (ref "U24") (pin "16") (pinfunction "OUT3_16") (pintype "open_collector"))
    )
    (net (code "54") (name "/T2-4") (class "Default")
      (node (ref "Rp7") (pin "5") (pinfunction "5_5") (pintype "passive"))
      (node (ref "Tube2") (pin "10") (pinfunction "d_10") (pintype "passive"))
      (node (ref "U24") (pin "15") (pinfunction "OUT4_15") (pintype "open_collector"))
    )
    (net (code "55") (name "/T2-5") (class "Default")
      (node (ref "Rp8") (pin "8") (pinfunction "8_8") (pintype "passive"))
      (node (ref "Tube2") (pin "9") (pinfunction "e_9") (pintype "passive"))
      (node (ref "U24") (pin "14") (pinfunction "OUT5_14") (pintype "open_collector"))
    )
    (net (code "56") (name "/T2-6") (class "Default")
      (node (ref "Rp8") (pin "7") (pinfunction "7_7") (pintype "passive"))
      (node (ref "Tube2") (pin "8") (pinfunction "f_8") (pintype "passive"))
      (node (ref "U24") (pin "13") (pinfunction "OUT6_13") (pintype "open_collector"))
    )
    (net (code "57") (name "/T2-7") (class "Default")
      (node (ref "Rp8") (pin "6") (pinfunction "6_6") (pintype "passive"))
      (node (ref "Tube2") (pin "7") (pinfunction "g_7") (pintype "passive"))
      (node (ref "U24") (pin "12") (pinfunction "OUT7_12") (pintype "open_collector"))
    )
    (net (code "58") (name "/T2-8") (class "Default")
      (node (ref "Rp8") (pin "5") (pinfunction "5_5") (pintype "passive"))
      (node (ref "Tube2") (pin "4") (pinfunction "h_4") (pintype "passive"))
      (node (ref "U24") (pin "11") (pinfunction "OUT8_11") (pintype "open_collector"))
    )
    (net (code "59") (name "/T3-1") (class "Default")
      (node (ref "Rp9") (pin "8") (pinfunction "8_8") (pintype "passive"))
      (node (ref "Tube3") (pin "6") (pinfunction "a_6") (pintype "passive"))
      (node (ref "U25") (pin "18") (pinfunction "OUT1_18") (pintype "open_collector"))
    )
    (net (code "60") (name "/T3-2") (class "Default")
      (node (ref "Rp9") (pin "7") (pinfunction "7_7") (pintype "passive"))
      (node (ref "Tube3") (pin "5") (pinfunction "b_5") (pintype "passive"))
      (node (ref "U25") (pin "17") (pinfunction "OUT2_17") (pintype "open_collector"))
    )
    (net (code "61") (name "/T3-3") (class "Default")
      (node (ref "Rp9") (pin "6") (pinfunction "6_6") (pintype "passive"))
      (node (ref "Tube3") (pin "3") (pinfunction "c_3") (pintype "passive"))
      (node (ref "U25") (pin "16") (pinfunction "OUT3_16") (pintype "open_collector"))
    )
    (net (code "62") (name "/T3-4") (class "Default")
      (node (ref "Rp9") (pin "5") (pinfunction "5_5") (pintype "passive"))
      (node (ref "Tube3") (pin "10") (pinfunction "d_10") (pintype "passive"))
      (node (ref "U25") (pin "15") (pinfunction "OUT4_15") (pintype "open_collector"))
    )
    (net (code "63") (name "/T3-5") (class "Default")
      (node (ref "Rp10") (pin "8") (pinfunction "8_8") (pintype "passive"))
      (node (ref "Tube3") (pin "9") (pinfunction "e_9") (pintype "passive"))
      (node (ref "U25") (pin "14") (pinfunction "OUT5_14") (pintype "open_collector"))
    )
    (net (code "64") (name "/T3-6") (class "Default")
      (node (ref "Rp10") (pin "7") (pinfunction "7_7") (pintype "passive"))
      (node (ref "Tube3") (pin "8") (pinfunction "f_8") (pintype "passive"))
      (node (ref "U25") (pin "13") (pinfunction "OUT6_13") (pintype "open_collector"))
    )
    (net (code "65") (name "/T3-7") (class "Default")
      (node (ref "Rp10") (pin "6") (pinfunction "6_6") (pintype "passive"))
      (node (ref "Tube3") (pin "7") (pinfunction "g_7") (pintype "passive"))
      (node (ref "U25") (pin "12") (pinfunction "OUT7_12") (pintype "open_collector"))
    )
    (net (code "66") (name "/T3-8") (class "Default")
      (node (ref "Rp10") (pin "5") (pinfunction "5_5") (pintype "passive"))
      (node (ref "Tube3") (pin "4") (pinfunction "h_4") (pintype "passive"))
      (node (ref "U25") (pin "11") (pinfunction "OUT8_11") (pintype "open_collector"))
    )
    (net (code "67") (name "/T4-1") (class "Default")
      (node (ref "Rp11") (pin "8") (pinfunction "8_8") (pintype "passive"))
      (node (ref "Tube4") (pin "6") (pinfunction "a_6") (pintype "passive"))
      (node (ref "U26") (pin "18") (pinfunction "OUT1_18") (pintype "open_collector"))
    )
    (net (code "68") (name "/T4-2") (class "Default")
      (node (ref "Rp11") (pin "7") (pinfunction "7_7") (pintype "passive"))
      (node (ref "Tube4") (pin "5") (pinfunction "b_5") (pintype "passive"))
      (node (ref "U26") (pin "17") (pinfunction "OUT2_17") (pintype "open_collector"))
    )
    (net (code "69") (name "/T4-3") (class "Default")
      (node (ref "Rp11") (pin "6") (pinfunction "6_6") (pintype "passive"))
      (node (ref "Tube4") (pin "3") (pinfunction "c_3") (pintype "passive"))
      (node (ref "U26") (pin "16") (pinfunction "OUT3_16") (pintype "open_collector"))
    )
    (net (code "70") (name "/T4-4") (class "Default")
      (node (ref "Rp11") (pin "5") (pinfunction "5_5") (pintype "passive"))
      (node (ref "Tube4") (pin "10") (pinfunction "d_10") (pintype "passive"))
      (node (ref "U26") (pin "15") (pinfunction "OUT4_15") (pintype "open_collector"))
    )
    (net (code "71") (name "/T4-5") (class "Default")
      (node (ref "Rp12") (pin "8") (pinfunction "8_8") (pintype "passive"))
      (node (ref "Tube4") (pin "9") (pinfunction "e_9") (pintype "passive"))
      (node (ref "U26") (pin "14") (pinfunction "OUT5_14") (pintype "open_collector"))
    )
    (net (code "72") (name "/T4-6") (class "Default")
      (node (ref "Rp12") (pin "7") (pinfunction "7_7") (pintype "passive"))
      (node (ref "Tube4") (pin "8") (pinfunction "f_8") (pintype "passive"))
      (node (ref "U26") (pin "13") (pinfunction "OUT6_13") (pintype "open_collector"))
    )
    (net (code "73") (name "/T4-7") (class "Default")
      (node (ref "Rp12") (pin "6") (pinfunction "6_6") (pintype "passive"))
      (node (ref "Tube4") (pin "7") (pinfunction "g_7") (pintype "passive"))
      (node (ref "U26") (pin "12") (pinfunction "OUT7_12") (pintype "open_collector"))
    )
    (net (code "74") (name "/T4-8") (class "Default")
      (node (ref "Rp12") (pin "5") (pinfunction "5_5") (pintype "passive"))
      (node (ref "Tube4") (pin "4") (pinfunction "h_4") (pintype "passive"))
      (node (ref "U26") (pin "11") (pinfunction "OUT8_11") (pintype "open_collector"))
    )
    (net (code "75") (name "/T5-1") (class "Default")
      (node (ref "Rp13") (pin "8") (pinfunction "8_8") (pintype "passive"))
      (node (ref "Tube5") (pin "6") (pinfunction "a_6") (pintype "passive"))
      (node (ref "U27") (pin "18") (pinfunction "OUT1_18") (pintype "open_collector"))
    )
    (net (code "76") (name "/T5-2") (class "Default")
      (node (ref "Rp13") (pin "7") (pinfunction "7_7") (pintype "passive"))
      (node (ref "Tube5") (pin "5") (pinfunction "b_5") (pintype "passive"))
      (node (ref "U27") (pin "17") (pinfunction "OUT2_17") (pintype "open_collector"))
    )
    (net (code "77") (name "/T5-3") (class "Default")
      (node (ref "Rp13") (pin "6") (pinfunction "6_6") (pintype "passive"))
      (node (ref "Tube5") (pin "3") (pinfunction "c_3") (pintype "passive"))
      (node (ref "U27") (pin "16") (pinfunction "OUT3_16") (pintype "open_collector"))
    )
    (net (code "78") (name "/T5-4") (class "Default")
      (node (ref "Rp13") (pin "5") (pinfunction "5_5") (pintype "passive"))
      (node (ref "Tube5") (pin "10") (pinfunction "d_10") (pintype "passive"))
      (node (ref "U27") (pin "15") (pinfunction "OUT4_15") (pintype "open_collector"))
    )
    (net (code "79") (name "/T5-5") (class "Default")
      (node (ref "Rp14") (pin "8") (pinfunction "8_8") (pintype "passive"))
      (node (ref "Tube5") (pin "9") (pinfunction "e_9") (pintype "passive"))
      (node (ref "U27") (pin "14") (pinfunction "OUT5_14") (pintype "open_collector"))
    )
    (net (code "80") (name "/T5-6") (class "Default")
      (node (ref "Rp14") (pin "7") (pinfunction "7_7") (pintype "passive"))
      (node (ref "Tube5") (pin "8") (pinfunction "f_8") (pintype "passive"))
      (node (ref "U27") (pin "13") (pinfunction "OUT6_13") (pintype "open_collector"))
    )
    (net (code "81") (name "/T5-7") (class "Default")
      (node (ref "Rp14") (pin "6") (pinfunction "6_6") (pintype "passive"))
      (node (ref "Tube5") (pin "7") (pinfunction "g_7") (pintype "passive"))
      (node (ref "U27") (pin "12") (pinfunction "OUT7_12") (pintype "open_collector"))
    )
    (net (code "82") (name "/T5-8") (class "Default")
      (node (ref "Rp14") (pin "5") (pinfunction "5_5") (pintype "passive"))
      (node (ref "Tube5") (pin "4") (pinfunction "h_4") (pintype "passive"))
      (node (ref "U27") (pin "11") (pinfunction "OUT8_11") (pintype "open_collector"))
    )
    (net (code "83") (name "/T6-1") (class "Default")
      (node (ref "Rp15") (pin "8") (pinfunction "8_8") (pintype "passive"))
      (node (ref "Tube6") (pin "6") (pinfunction "a_6") (pintype "passive"))
      (node (ref "U28") (pin "18") (pinfunction "OUT1_18") (pintype "open_collector"))
    )
    (net (code "84") (name "/T6-2") (class "Default")
      (node (ref "Rp15") (pin "7") (pinfunction "7_7") (pintype "passive"))
      (node (ref "Tube6") (pin "5") (pinfunction "b_5") (pintype "passive"))
      (node (ref "U28") (pin "17") (pinfunction "OUT2_17") (pintype "open_collector"))
    )
    (net (code "85") (name "/T6-3") (class "Default")
      (node (ref "Rp15") (pin "6") (pinfunction "6_6") (pintype "passive"))
      (node (ref "Tube6") (pin "3") (pinfunction "c_3") (pintype "passive"))
      (node (ref "U28") (pin "16") (pinfunction "OUT3_16") (pintype "open_collector"))
    )
    (net (code "86") (name "/T6-4") (class "Default")
      (node (ref "Rp15") (pin "5") (pinfunction "5_5") (pintype "passive"))
      (node (ref "Tube6") (pin "10") (pinfunction "d_10") (pintype "passive"))
      (node (ref "U28") (pin "15") (pinfunction "OUT4_15") (pintype "open_collector"))
    )
    (net (code "87") (name "/T6-5") (class "Default")
      (node (ref "Rp16") (pin "8") (pinfunction "8_8") (pintype "passive"))
      (node (ref "Tube6") (pin "9") (pinfunction "e_9") (pintype "passive"))
      (node (ref "U28") (pin "14") (pinfunction "OUT5_14") (pintype "open_collector"))
    )
    (net (code "88") (name "/T6-6") (class "Default")
      (node (ref "Rp16") (pin "7") (pinfunction "7_7") (pintype "passive"))
      (node (ref "Tube6") (pin "8") (pinfunction "f_8") (pintype "passive"))
      (node (ref "U28") (pin "13") (pinfunction "OUT6_13") (pintype "open_collector"))
    )
    (net (code "89") (name "/T6-7") (class "Default")
      (node (ref "Rp16") (pin "6") (pinfunction "6_6") (pintype "passive"))
      (node (ref "Tube6") (pin "7") (pinfunction "g_7") (pintype "passive"))
      (node (ref "U28") (pin "12") (pinfunction "OUT7_12") (pintype "open_collector"))
    )
    (net (code "90") (name "/T6-8") (class "Default")
      (node (ref "Rp16") (pin "5") (pinfunction "5_5") (pintype "passive"))
      (node (ref "Tube6") (pin "4") (pinfunction "h_4") (pintype "passive"))
      (node (ref "U28") (pin "11") (pinfunction "OUT8_11") (pintype "open_collector"))
    )
    (net (code "91") (name "/TX1") (class "Default")
      (node (ref "U1") (pin "30") (pinfunction "PA9_30") (pintype "bidirectional"))
      (node (ref "U16") (pin "3") (pinfunction "RXD_3") (pintype "passive"))
    )
    (net (code "92") (name "/UD+") (class "Default")
      (node (ref "P1") (pin "1") (pinfunction "1_1") (pintype "passive"))
      (node (ref "U16") (pin "5") (pinfunction "UD+_5") (pintype "passive"))
    )
    (net (code "93") (name "/UD-") (class "Default")
      (node (ref "P1") (pin "2") (pinfunction "2_2") (pintype "passive"))
      (node (ref "U16") (pin "6") (pinfunction "UD-_6") (pintype "passive"))
    )
    (net (code "94") (name "/USB-Ctl") (class "Default")
      (node (ref "R9") (pin "1") (pinfunction "1_1") (pintype "passive"))
      (node (ref "U1") (pin "29") (pinfunction "PA8_29") (pintype "bidirectional"))
    )
    (net (code "95") (name "/USB_N") (class "Default")
      (node (ref "R6") (pin "1") (pinfunction "1_1") (pintype "passive"))
      (node (ref "U1") (pin "32") (pinfunction "PA11_32") (pintype "bidirectional"))
    )
    (net (code "96") (name "/USB_P") (class "Default")
      (node (ref "R11") (pin "2") (pinfunction "2_2") (pintype "passive"))
      (node (ref "R5") (pin "2") (pinfunction "2_2") (pintype "passive"))
      (node (ref "U1") (pin "33") (pinfunction "PA12_33") (pintype "bidirectional"))
    )
    (net (code "97") (name "GND") (class "Default")
      (node (ref "*1") (pin "2") (pinfunction "VSS_2") (pintype "passive"))
      (node (ref "BT1") (pin "2") (pinfunction "-_2") (pintype "passive"))
      (node (ref "C1") (pin "2") (pinfunction "2_2") (pintype "passive"))
      (node (ref "C10") (pin "1") (pinfunction "1_1") (pintype "passive"))
      (node (ref "C11") (pin "2") (pinfunction "2_2") (pintype "passive"))
      (node (ref "C12") (pin "2") (pinfunction "2_2") (pintype "passive"))
      (node (ref "C13") (pin "2") (pinfunction "2_2") (pintype "passive"))
      (node (ref "C14") (pin "2") (pinfunction "2_2") (pintype "passive"))
      (node (ref "C15") (pin "2") (pinfunction "2_2") (pintype "passive"))
      (node (ref "C16") (pin "2") (pinfunction "2_2") (pintype "passive"))
      (node (ref "C17") (pin "1") (pinfunction "1_1") (pintype "passive"))
      (node (ref "C18") (pin "1") (pinfunction "1_1") (pintype "passive"))
      (node (ref "C19") (pin "1") (pinfunction "1_1") (pintype "passive"))
      (node (ref "C2") (pin "1") (pinfunction "1_1") (pintype "passive"))
      (node (ref "C20") (pin "1") (pinfunction "1_1") (pintype "passive"))
      (node (ref "C21") (pin "2") (pinfunction "2_2") (pintype "passive"))
      (node (ref "C22") (pin "2") (pinfunction "2_2") (pintype "passive"))
      (node (ref "C23") (pin "1") (pinfunction "1_1") (pintype "passive"))
      (node (ref "C24") (pin "1") (pinfunction "1_1") (pintype "passive"))
      (node (ref "C25") (pin "1") (pinfunction "1_1") (pintype "passive"))
      (node (ref "C26") (pin "1") (pinfunction "1_1") (pintype "passive"))
      (node (ref "C27") (pin "2") (pinfunction "2_2") (pintype "passive"))
      (node (ref "C28") (pin "2") (pinfunction "2_2") (pintype "passive"))
      (node (ref "C29") (pin "2") (pinfunction "2_2") (pintype "passive"))
      (node (ref "C3") (pin "1") (pinfunction "1_1") (pintype "passive"))
      (node (ref "C30") (pin "2") (pinfunction "2_2") (pintype "passive"))
      (node (ref "C31") (pin "2") (pinfunction "2_2") (pintype "passive"))
      (node (ref "C32") (pin "2") (pinfunction "2_2") (pintype "passive"))
      (node (ref "C33") (pin "1") (pinfunction "1_1") (pintype "passive"))
      (node (ref "C4") (pin "1") (pinfunction "1_1") (pintype "passive"))
      (node (ref "C5") (pin "1") (pinfunction "1_1") (pintype "passive"))
      (node (ref "C6") (pin "2") (pinfunction "2_2") (pintype "passive"))
      (node (ref "C7") (pin "2") (pinfunction "2_2") (pintype "passive"))
      (node (ref "C8") (pin "1") (pinfunction "1_1") (pintype "passive"))
      (node (ref "C9") (pin "2") (pinfunction "2_2") (pintype "passive"))
      (node (ref "D4") (pin "1") (pinfunction "A_1") (pintype "passive"))
      (node (ref "J1") (pin "5") (pinfunction "VSS_5") (pintype "passive"))
      (node (ref "P2") (pin "2") (pinfunction "2_2") (pintype "passive"))
      (node (ref "P3") (pin "2") (pinfunction "2_2") (pintype "passive"))
      (node (ref "Q2") (pin "2") (pinfunction "E_2") (pintype "passive"))
      (node (ref "R10") (pin "1") (pinfunction "1_1") (pintype "passive"))
      (node (ref "R13") (pin "1") (pinfunction "1_1") (pintype "passive"))
      (node (ref "R19") (pin "1") (pinfunction "1_1") (pintype "passive"))
      (node (ref "R21") (pin "1") (pinfunction "1_1") (pintype "passive"))
      (node (ref "T1") (pin "1") (pinfunction "1_1") (pintype "passive"))
      (node (ref "T2") (pin "1") (pinfunction "1_1") (pintype "passive"))
      (node (ref "T3") (pin "1") (pinfunction "1_1") (pintype "passive"))
      (node (ref "T4") (pin "1") (pinfunction "1_1") (pintype "passive"))
      (node (ref "T5") (pin "1") (pinfunction "1_1") (pintype "passive"))
      (node (ref "Tube2") (pin "11") (pinfunction "11_11") (pintype "passive"))
      (node (ref "Tube4") (pin "11") (pinfunction "11_11") (pintype "passive"))
      (node (ref "Tube6") (pin "11") (pinfunction "11_11") (pintype "passive"))
      (node (ref "U1") (pin "23") (pinfunction "VSS_1_23") (pintype "power_in"))
      (node (ref "U1") (pin "35") (pinfunction "VSS_2_35") (pintype "power_in"))
      (node (ref "U1") (pin "47") (pinfunction "VSS_3_47") (pintype "power_in"))
      (node (ref "U1") (pin "8") (pinfunction "VSSA_8") (pintype "power_in"))
      (node (ref "U10") (pin "3") (pinfunction "VSS_3") (pintype "passive"))
      (node (ref "U11") (pin "3") (pinfunction "VSS_3") (pintype "passive"))
      (node (ref "U12") (pin "3") (pinfunction "VSS_3") (pintype "passive"))
      (node (ref "U13") (pin "2") (pinfunction "GND_2") (pintype "passive"))
      (node (ref "U14") (pin "4") (pinfunction "GND_4") (pintype "passive"))
      (node (ref "U15") (pin "4") (pinfunction "GND_4") (pintype "passive"))
      (node (ref "U16") (pin "1") (pinfunction "GND_1") (pintype "passive"))
      (node (ref "U17") (pin "8") (pinfunction "GND_8") (pintype "power_in"))
      (node (ref "U18") (pin "8") (pinfunction "GND_8") (pintype "power_in"))
      (node (ref "U19") (pin "8") (pinfunction "GND_8") (pintype "power_in"))
      (node (ref "U2") (pin "2") (pinfunction "GND_2") (pintype "passive"))
      (node (ref "U20") (pin "8") (pinfunction "GND_8") (pintype "power_in"))
      (node (ref "U21") (pin "8") (pinfunction "GND_8") (pintype "power_in"))
      (node (ref "U22") (pin "8") (pinfunction "GND_8") (pintype "power_in"))
      (node (ref "U23") (pin "9") (pinfunction "GND_9") (pintype "power_in"))
      (node (ref "U24") (pin "9") (pinfunction "GND_9") (pintype "power_in"))
      (node (ref "U25") (pin "9") (pinfunction "GND_9") (pintype "power_in"))
      (node (ref "U26") (pin "9") (pinfunction "GND_9") (pintype "power_in"))
      (node (ref "U27") (pin "9") (pinfunction "GND_9") (pintype "power_in"))
      (node (ref "U28") (pin "9") (pinfunction "GND_9") (pintype "power_in"))
      (node (ref "U29") (pin "10") (pinfunction "N.C._10") (pintype "passive"))
      (node (ref "U29") (pin "11") (pinfunction "N.C._11") (pintype "passive"))
      (node (ref "U29") (pin "12") (pinfunction "N.C._12") (pintype "passive"))
      (node (ref "U29") (pin "13") (pinfunction "GND_13") (pintype "passive"))
      (node (ref "U29") (pin "5") (pinfunction "N.C._5") (pintype "passive"))
      (node (ref "U29") (pin "6") (pinfunction "N.C._6") (pintype "passive"))
      (node (ref "U29") (pin "7") (pinfunction "N.C._7") (pintype "passive"))
      (node (ref "U29") (pin "8") (pinfunction "N.C._8") (pintype "passive"))
      (node (ref "U29") (pin "9") (pinfunction "N.C._9") (pintype "passive"))
      (node (ref "U3") (pin "2") (pinfunction "GND_2") (pintype "passive"))
      (node (ref "U4") (pin "2") (pinfunction "SWE_2") (pintype "passive"))
      (node (ref "U4") (pin "4") (pinfunction "GND_4") (pintype "passive"))
      (node (ref "U5") (pin "9") (pinfunction "GND_9") (pintype "passive"))
      (node (ref "U6") (pin "4") (pinfunction "GND_4") (pintype "passive"))
      (node (ref "U7") (pin "3") (pinfunction "VSS_3") (pintype "passive"))
      (node (ref "U8") (pin "3") (pinfunction "VSS_3") (pintype "passive"))
      (node (ref "U9") (pin "3") (pinfunction "VSS_3") (pintype "passive"))
      (node (ref "VR1") (pin "1") (pinfunction "GND_1") (pintype "passive"))
    )
    (net (code "98") (name "Net-(BT1-+)") (class "Default")
      (node (ref "BT1") (pin "1") (pinfunction "+_1") (pintype "passive"))
      (node (ref "U29") (pin "14") (pinfunction "VBAT_14") (pintype "passive"))
    )
    (net (code "99") (name "Net-(D1-PadK)") (class "Default")
      (node (ref "D1") (pin "K") (pinfunction "K_K") (pintype "passive"))
      (node (ref "R8") (pin "1") (pinfunction "1_1") (pintype "passive"))
    )
    (net (code "100") (name "Net-(D2-A)") (class "Default")
      (node (ref "D2") (pin "1") (pinfunction "A_1") (pintype "passive"))
      (node (ref "L1") (pin "2") (pinfunction "2_2") (pintype "passive"))
      (node (ref "U4") (pin "1") (pinfunction "SWC_1") (pintype "passive"))
    )
    (net (code "101") (name "Net-(D3-PadK)") (class "Default")
      (node (ref "D3") (pin "K") (pinfunction "K_K") (pintype "passive"))
      (node (ref "R18") (pin "1") (pinfunction "1_1") (pintype "passive"))
    )
    (net (code "102") (name "Net-(D4-K)") (class "Default")
      (node (ref "D4") (pin "2") (pinfunction "K_2") (pintype "passive"))
      (node (ref "L2") (pin "2") (pinfunction "2_2") (pintype "passive"))
      (node (ref "U6") (pin "2") (pinfunction "SWE_2") (pintype "passive"))
    )
    (net (code "103") (name "Net-(D5-A)") (class "Default")
      (node (ref "D5") (pin "1") (pinfunction "A_1") (pintype "passive"))
      (node (ref "J2") (pin "2") (pinfunction "1_2") (pintype "passive"))
      (node (ref "Q2") (pin "3") (pinfunction "C_3") (pintype "passive"))
    )
    (net (code "104") (name "Net-(P1-Pad5)") (class "Default")
      (node (ref "P1") (pin "5") (pinfunction "5_5") (pintype "passive"))
      (node (ref "R5") (pin "1") (pinfunction "1_1") (pintype "passive"))
    )
    (net (code "105") (name "Net-(P1-Pad6)") (class "Default")
      (node (ref "P1") (pin "6") (pinfunction "6_6") (pintype "passive"))
      (node (ref "R6") (pin "2") (pinfunction "2_2") (pintype "passive"))
    )
    (net (code "106") (name "Net-(Q1-B)") (class "Default")
      (node (ref "Q1") (pin "1") (pinfunction "B_1") (pintype "passive"))
      (node (ref "R9") (pin "2") (pinfunction "2_2") (pintype "passive"))
    )
    (net (code "107") (name "Net-(Q1-E)") (class "Default")
      (node (ref "Q1") (pin "2") (pinfunction "E_2") (pintype "passive"))
      (node (ref "R11") (pin "1") (pinfunction "1_1") (pintype "passive"))
    )
    (net (code "108") (name "Net-(Q2-B)") (class "Default")
      (node (ref "Q2") (pin "1") (pinfunction "B_1") (pintype "passive"))
      (node (ref "R20") (pin "2") (pinfunction "2_2") (pintype "passive"))
      (node (ref "R21") (pin "2") (pinfunction "2_2") (pintype "passive"))
    )
    (net (code "109") (name "Net-(R17-Pad1)") (class "Default")
      (node (ref "R17") (pin "1") (pinfunction "1_1") (pintype "passive"))
      (node (ref "S2") (pin "1") (pinfunction "1_1") (pintype "passive"))
    )
    (net (code "110") (name "Net-(Tube1-Pad11)") (class "Default")
      (node (ref "Tube1") (pin "11") (pinfunction "11_11") (pintype "passive"))
      (node (ref "Tube2") (pin "1") (pinfunction "1_1") (pintype "passive"))
    )
    (net (code "111") (name "Net-(Tube3-Pad11)") (class "Default")
      (node (ref "Tube3") (pin "11") (pinfunction "11_11") (pintype "passive"))
      (node (ref "Tube4") (pin "1") (pinfunction "1_1") (pintype "passive"))
    )
    (net (code "112") (name "Net-(Tube5-Pad11)") (class "Default")
      (node (ref "Tube5") (pin "11") (pinfunction "11_11") (pintype "passive"))
      (node (ref "Tube6") (pin "1") (pinfunction "1_1") (pintype "passive"))
    )
    (net (code "113") (name "Net-(U1A-BOOT0)") (class "Default")
      (node (ref "R13") (pin "2") (pinfunction "2_2") (pintype "passive"))
      (node (ref "S2") (pin "2") (pinfunction "2_2") (pintype "passive"))
      (node (ref "U1") (pin "44") (pinfunction "BOOT0_44") (pintype "input"))
    )
    (net (code "114") (name "Net-(U2-OCB)") (class "Default")
      (node (ref "R3") (pin "1") (pinfunction "1_1") (pintype "passive"))
      (node (ref "U2") (pin "3") (pinfunction "OCB_3") (pintype "passive"))
    )
    (net (code "115") (name "Net-(U2-OUT)") (class "Default")
      (node (ref "C13") (pin "1") (pinfunction "1_1") (pintype "passive"))
      (node (ref "C16") (pin "1") (pinfunction "1_1") (pintype "passive"))
      (node (ref "U2") (pin "1") (pinfunction "OUT_1") (pintype "passive"))
      (node (ref "U5") (pin "8") (pinfunction "VCC_8") (pintype "passive"))
    )
    (net (code "116") (name "Net-(U3-OCB)") (class "Default")
      (node (ref "R4") (pin "1") (pinfunction "1_1") (pintype "passive"))
      (node (ref "U3") (pin "3") (pinfunction "OCB_3") (pintype "passive"))
    )
    (net (code "117") (name "Net-(U4-DRVC)") (class "Default")
      (node (ref "R1") (pin "1") (pinfunction "1_1") (pintype "passive"))
      (node (ref "U4") (pin "8") (pinfunction "DRVC_8") (pintype "passive"))
    )
    (net (code "118") (name "Net-(U4-IN-)") (class "Default")
      (node (ref "R10") (pin "2") (pinfunction "2_2") (pintype "passive"))
      (node (ref "R7") (pin "1") (pinfunction "1_1") (pintype "passive"))
      (node (ref "U4") (pin "5") (pinfunction "IN-_5") (pintype "passive"))
    )
    (net (code "119") (name "Net-(U4-IPK)") (class "Default")
      (node (ref "L1") (pin "1") (pinfunction "1_1") (pintype "passive"))
      (node (ref "R1") (pin "2") (pinfunction "2_2") (pintype "passive"))
      (node (ref "R2") (pin "1") (pinfunction "1_1") (pintype "passive"))
      (node (ref "U4") (pin "7") (pinfunction "IPK_7") (pintype "passive"))
    )
    (net (code "120") (name "Net-(U4-Tcap)") (class "Default")
      (node (ref "C8") (pin "2") (pinfunction "2_2") (pintype "passive"))
      (node (ref "U4") (pin "3") (pinfunction "Tcap_3") (pintype "passive"))
    )
    (net (code "121") (name "Net-(U6-DRVC)") (class "Default")
      (node (ref "R15") (pin "1") (pinfunction "1_1") (pintype "passive"))
      (node (ref "U6") (pin "1") (pinfunction "SWC_1") (pintype "passive"))
      (node (ref "U6") (pin "7") (pinfunction "IPK_7") (pintype "passive"))
      (node (ref "U6") (pin "8") (pinfunction "DRVC_8") (pintype "passive"))
    )
    (net (code "122") (name "Net-(U6-IN-)") (class "Default")
      (node (ref "R16") (pin "1") (pinfunction "1_1") (pintype "passive"))
      (node (ref "R19") (pin "2") (pinfunction "2_2") (pintype "passive"))
      (node (ref "U6") (pin "5") (pinfunction "IN-_5") (pintype "passive"))
    )
    (net (code "123") (name "Net-(U6-Tcap)") (class "Default")
      (node (ref "C17") (pin "2") (pinfunction "2_2") (pintype "passive"))
      (node (ref "U6") (pin "3") (pinfunction "Tcap_3") (pintype "passive"))
    )
    (net (code "124") (name "Net-(U7-DO)") (class "Default")
      (node (ref "U7") (pin "2") (pinfunction "DO_2") (pintype "passive"))
      (node (ref "U8") (pin "4") (pinfunction "DI_4") (pintype "passive"))
    )
    (net (code "125") (name "Net-(U8-DO)") (class "Default")
      (node (ref "U8") (pin "2") (pinfunction "DO_2") (pintype "passive"))
      (node (ref "U9") (pin "4") (pinfunction "DI_4") (pintype "passive"))
    )
    (net (code "126") (name "Net-(U10-DI)") (class "Default")
      (node (ref "U10") (pin "4") (pinfunction "DI_4") (pintype "passive"))
      (node (ref "U9") (pin "2") (pinfunction "DO_2") (pintype "passive"))
    )
    (net (code "127") (name "Net-(U10-DO)") (class "Default")
      (node (ref "U10") (pin "2") (pinfunction "DO_2") (pintype "passive"))
      (node (ref "U11") (pin "4") (pinfunction "DI_4") (pintype "passive"))
    )
    (net (code "128") (name "Net-(U11-DO)") (class "Default")
      (node (ref "U11") (pin "2") (pinfunction "DO_2") (pintype "passive"))
      (node (ref "U12") (pin "4") (pinfunction "DI_4") (pintype "passive"))
    )
    (net (code "129") (name "Net-(U14-DO)") (class "Default")
      (node (ref "U14") (pin "5") (pinfunction "DO_5") (pintype "passive"))
      (node (ref "U15") (pin "6") (pinfunction "DI_6") (pintype "passive"))
    )
    (net (code "130") (name "Net-(U16-V3.3)") (class "Default")
      (node (ref "C25") (pin "2") (pinfunction "2_2") (pintype "passive"))
      (node (ref "U16") (pin "4") (pinfunction "V3.3_4") (pintype "passive"))
    )
    (net (code "131") (name "Net-(U17-QA)") (class "Default")
      (node (ref "U17") (pin "15") (pinfunction "QA_15") (pintype "tri_state"))
      (node (ref "U23") (pin "1") (pinfunction "IN1_1") (pintype "input"))
    )
    (net (code "132") (name "Net-(U17-QB)") (class "Default")
      (node (ref "U17") (pin "1") (pinfunction "QB_1") (pintype "tri_state"))
      (node (ref "U23") (pin "2") (pinfunction "IN2_2") (pintype "input"))
    )
    (net (code "133") (name "Net-(U17-QC)") (class "Default")
      (node (ref "U17") (pin "2") (pinfunction "QC_2") (pintype "tri_state"))
      (node (ref "U23") (pin "3") (pinfunction "IN3_3") (pintype "input"))
    )
    (net (code "134") (name "Net-(U17-QD)") (class "Default")
      (node (ref "U17") (pin "3") (pinfunction "QD_3") (pintype "tri_state"))
      (node (ref "U23") (pin "4") (pinfunction "IN4_4") (pintype "input"))
    )
    (net (code "135") (name "Net-(U17-QE)") (class "Default")
      (node (ref "U17") (pin "4") (pinfunction "QE_4") (pintype "tri_state"))
      (node (ref "U23") (pin "5") (pinfunction "IN5_5") (pintype "input"))
    )
    (net (code "136") (name "Net-(U17-QF)") (class "Default")
      (node (ref "U17") (pin "5") (pinfunction "QF_5") (pintype "tri_state"))
      (node (ref "U23") (pin "6") (pinfunction "IN6_6") (pintype "input"))
    )
    (net (code "137") (name "Net-(U17-QG)") (class "Default")
      (node (ref "U17") (pin "6") (pinfunction "QG_6") (pintype "tri_state"))
      (node (ref "U23") (pin "7") (pinfunction "IN7_7") (pintype "input"))
    )
    (net (code "138") (name "Net-(U17-QH)") (class "Default")
      (node (ref "U17") (pin "7") (pinfunction "QH_7") (pintype "tri_state"))
      (node (ref "U23") (pin "8") (pinfunction "IN8_8") (pintype "input"))
    )
    (net (code "139") (name "Net-(U18-QA)") (class "Default")
      (node (ref "U18") (pin "15") (pinfunction "QA_15") (pintype "tri_state"))
      (node (ref "U24") (pin "1") (pinfunction "IN1_1") (pintype "input"))
    )
    (net (code "140") (name "Net-(U18-QB)") (class "Default")
      (node (ref "U18") (pin "1") (pinfunction "QB_1") (pintype "tri_state"))
      (node (ref "U24") (pin "2") (pinfunction "IN2_2") (pintype "input"))
    )
    (net (code "141") (name "Net-(U18-QC)") (class "Default")
      (node (ref "U18") (pin "2") (pinfunction "QC_2") (pintype "tri_state"))
      (node (ref "U24") (pin "3") (pinfunction "IN3_3") (pintype "input"))
    )
    (net (code "142") (name "Net-(U18-QD)") (class "Default")
      (node (ref "U18") (pin "3") (pinfunction "QD_3") (pintype "tri_state"))
      (node (ref "U24") (pin "4") (pinfunction "IN4_4") (pintype "input"))
    )
    (net (code "143") (name "Net-(U18-QE)") (class "Default")
      (node (ref "U18") (pin "4") (pinfunction "QE_4") (pintype "tri_state"))
      (node (ref "U24") (pin "5") (pinfunction "IN5_5") (pintype "input"))
    )
    (net (code "144") (name "Net-(U18-QF)") (class "Default")
      (node (ref "U18") (pin "5") (pinfunction "QF_5") (pintype "tri_state"))
      (node (ref "U24") (pin "6") (pinfunction "IN6_6") (pintype "input"))
    )
    (net (code "145") (name "Net-(U18-QG)") (class "Default")
      (node (ref "U18") (pin "6") (pinfunction "QG_6") (pintype "tri_state"))
      (node (ref "U24") (pin "7") (pinfunction "IN7_7") (pintype "input"))
    )
    (net (code "146") (name "Net-(U18-QH)") (class "Default")
      (node (ref "U18") (pin "7") (pinfunction "QH_7") (pintype "tri_state"))
      (node (ref "U24") (pin "8") (pinfunction "IN8_8") (pintype "input"))
    )
    (net (code "147") (name "Net-(U19-QA)") (class "Default")
      (node (ref "U19") (pin "15") (pinfunction "QA_15") (pintype "tri_state"))
      (node (ref "U25") (pin "1") (pinfunction "IN1_1") (pintype "input"))
    )
    (net (code "148") (name "Net-(U19-QB)") (class "Default")
      (node (ref "U19") (pin "1") (pinfunction "QB_1") (pintype "tri_state"))
      (node (ref "U25") (pin "2") (pinfunction "IN2_2") (pintype "input"))
    )
    (net (code "149") (name "Net-(U19-QC)") (class "Default")
      (node (ref "U19") (pin "2") (pinfunction "QC_2") (pintype "tri_state"))
      (node (ref "U25") (pin "3") (pinfunction "IN3_3") (pintype "input"))
    )
    (net (code "150") (name "Net-(U19-QD)") (class "Default")
      (node (ref "U19") (pin "3") (pinfunction "QD_3") (pintype "tri_state"))
      (node (ref "U25") (pin "4") (pinfunction "IN4_4") (pintype "input"))
    )
    (net (code "151") (name "Net-(U19-QE)") (class "Default")
      (node (ref "U19") (pin "4") (pinfunction "QE_4") (pintype "tri_state"))
      (node (ref "U25") (pin "5") (pinfunction "IN5_5") (pintype "input"))
    )
    (net (code "152") (name "Net-(U19-QF)") (class "Default")
      (node (ref "U19") (pin "5") (pinfunction "QF_5") (pintype "tri_state"))
      (node (ref "U25") (pin "6") (pinfunction "IN6_6") (pintype "input"))
    )
    (net (code "153") (name "Net-(U19-QG)") (class "Default")
      (node (ref "U19") (pin "6") (pinfunction "QG_6") (pintype "tri_state"))
      (node (ref "U25") (pin "7") (pinfunction "IN7_7") (pintype "input"))
    )
    (net (code "154") (name "Net-(U19-QH)") (class "Default")
      (node (ref "U19") (pin "7") (pinfunction "QH_7") (pintype "tri_state"))
      (node (ref "U25") (pin "8") (pinfunction "IN8_8") (pintype "input"))
    )
    (net (code "155") (name "Net-(U20-QA)") (class "Default")
      (node (ref "U20") (pin "15") (pinfunction "QA_15") (pintype "tri_state"))
      (node (ref "U26") (pin "1") (pinfunction "IN1_1") (pintype "input"))
    )
    (net (code "156") (name "Net-(U20-QB)") (class "Default")
      (node (ref "U20") (pin "1") (pinfunction "QB_1") (pintype "tri_state"))
      (node (ref "U26") (pin "2") (pinfunction "IN2_2") (pintype "input"))
    )
    (net (code "157") (name "Net-(U20-QC)") (class "Default")
      (node (ref "U20") (pin "2") (pinfunction "QC_2") (pintype "tri_state"))
      (node (ref "U26") (pin "3") (pinfunction "IN3_3") (pintype "input"))
    )
    (net (code "158") (name "Net-(U20-QD)") (class "Default")
      (node (ref "U20") (pin "3") (pinfunction "QD_3") (pintype "tri_state"))
      (node (ref "U26") (pin "4") (pinfunction "IN4_4") (pintype "input"))
    )
    (net (code "159") (name "Net-(U20-QE)") (class "Default")
      (node (ref "U20") (pin "4") (pinfunction "QE_4") (pintype "tri_state"))
      (node (ref "U26") (pin "5") (pinfunction "IN5_5") (pintype "input"))
    )
    (net (code "160") (name "Net-(U20-QF)") (class "Default")
      (node (ref "U20") (pin "5") (pinfunction "QF_5") (pintype "tri_state"))
      (node (ref "U26") (pin "6") (pinfunction "IN6_6") (pintype "input"))
    )
    (net (code "161") (name "Net-(U20-QG)") (class "Default")
      (node (ref "U20") (pin "6") (pinfunction "QG_6") (pintype "tri_state"))
      (node (ref "U26") (pin "7") (pinfunction "IN7_7") (pintype "input"))
    )
    (net (code "162") (name "Net-(U20-QH)") (class "Default")
      (node (ref "U20") (pin "7") (pinfunction "QH_7") (pintype "tri_state"))
      (node (ref "U26") (pin "8") (pinfunction "IN8_8") (pintype "input"))
    )
    (net (code "163") (name "Net-(U21-QA)") (class "Default")
      (node (ref "U21") (pin "15") (pinfunction "QA_15") (pintype "tri_state"))
      (node (ref "U27") (pin "1") (pinfunction "IN1_1") (pintype "input"))
    )
    (net (code "164") (name "Net-(U21-QB)") (class "Default")
      (node (ref "U21") (pin "1") (pinfunction "QB_1") (pintype "tri_state"))
      (node (ref "U27") (pin "2") (pinfunction "IN2_2") (pintype "input"))
    )
    (net (code "165") (name "Net-(U21-QC)") (class "Default")
      (node (ref "U21") (pin "2") (pinfunction "QC_2") (pintype "tri_state"))
      (node (ref "U27") (pin "3") (pinfunction "IN3_3") (pintype "input"))
    )
    (net (code "166") (name "Net-(U21-QD)") (class "Default")
      (node (ref "U21") (pin "3") (pinfunction "QD_3") (pintype "tri_state"))
      (node (ref "U27") (pin "4") (pinfunction "IN4_4") (pintype "input"))
    )
    (net (code "167") (name "Net-(U21-QE)") (class "Default")
      (node (ref "U21") (pin "4") (pinfunction "QE_4") (pintype "tri_state"))
      (node (ref "U27") (pin "5") (pinfunction "IN5_5") (pintype "input"))
    )
    (net (code "168") (name "Net-(U21-QF)") (class "Default")
      (node (ref "U21") (pin "5") (pinfunction "QF_5") (pintype "tri_state"))
      (node (ref "U27") (pin "6") (pinfunction "IN6_6") (pintype "input"))
    )
    (net (code "169") (name "Net-(U21-QG)") (class "Default")
      (node (ref "U21") (pin "6") (pinfunction "QG_6") (pintype "tri_state"))
      (node (ref "U27") (pin "7") (pinfunction "IN7_7") (pintype "input"))
    )
    (net (code "170") (name "Net-(U21-QH)") (class "Default")
      (node (ref "U21") (pin "7") (pinfunction "QH_7") (pintype "tri_state"))
      (node (ref "U27") (pin "8") (pinfunction "IN8_8") (pintype "input"))
    )
    (net (code "171") (name "Net-(U22-QA)") (class "Default")
      (node (ref "U22") (pin "15") (pinfunction "QA_15") (pintype "tri_state"))
      (node (ref "U28") (pin "1") (pinfunction "IN1_1") (pintype "input"))
    )
    (net (code "172") (name "Net-(U22-QB)") (class "Default")
      (node (ref "U22") (pin "1") (pinfunction "QB_1") (pintype "tri_state"))
      (node (ref "U28") (pin "2") (pinfunction "IN2_2") (pintype "input"))
    )
    (net (code "173") (name "Net-(U22-QC)") (class "Default")
      (node (ref "U22") (pin "2") (pinfunction "QC_2") (pintype "tri_state"))
      (node (ref "U28") (pin "3") (pinfunction "IN3_3") (pintype "input"))
    )
    (net (code "174") (name "Net-(U22-QD)") (class "Default")
      (node (ref "U22") (pin "3") (pinfunction "QD_3") (pintype "tri_state"))
      (node (ref "U28") (pin "4") (pinfunction "IN4_4") (pintype "input"))
    )
    (net (code "175") (name "Net-(U22-QE)") (class "Default")
      (node (ref "U22") (pin "4") (pinfunction "QE_4") (pintype "tri_state"))
      (node (ref "U28") (pin "5") (pinfunction "IN5_5") (pintype "input"))
    )
    (net (code "176") (name "Net-(U22-QF)") (class "Default")
      (node (ref "U22") (pin "5") (pinfunction "QF_5") (pintype "tri_state"))
      (node (ref "U28") (pin "6") (pinfunction "IN6_6") (pintype "input"))
    )
    (net (code "177") (name "Net-(U22-QG)") (class "Default")
      (node (ref "U22") (pin "6") (pinfunction "QG_6") (pintype "tri_state"))
      (node (ref "U28") (pin "7") (pinfunction "IN7_7") (pintype "input"))
    )
    (net (code "178") (name "Net-(U22-QH)") (class "Default")
      (node (ref "U22") (pin "7") (pinfunction "QH_7") (pintype "tri_state"))
      (node (ref "U28") (pin "8") (pinfunction "IN8_8") (pintype "input"))
    )
    (net (code "179") (name "unconnected-(*1-NC-Pad3)") (class "Default")
      (node (ref "*1") (pin "3") (pinfunction "NC_3") (pintype "passive"))
    )
    (net (code "180") (name "unconnected-(*1-NC-Pad4)") (class "Default")
      (node (ref "*1") (pin "4") (pinfunction "NC_4") (pintype "passive"))
    )
    (net (code "181") (name "unconnected-(J1-ID-Pad4)") (class "Default")
      (node (ref "J1") (pin "4") (pinfunction "ID_4") (pintype "passive"))
    )
    (net (code "182") (name "unconnected-(Rp2-Pad4)") (class "Default")
      (node (ref "Rp2") (pin "4") (pinfunction "4_4") (pintype "passive"))
    )
    (net (code "183") (name "unconnected-(Rp3-Pad1)") (class "Default")
      (node (ref "Rp3") (pin "1") (pinfunction "1_1") (pintype "passive"))
    )
    (net (code "184") (name "unconnected-(Rp4-Pad1)") (class "Default")
      (node (ref "Rp4") (pin "1") (pinfunction "1_1") (pintype "passive"))
    )
    (net (code "185") (name "unconnected-(U1A-PA0-WKUP-Pad10)") (class "Default")
      (node (ref "U1") (pin "10") (pinfunction "PA0-WKUP_10") (pintype "bidirectional"))
    )
    (net (code "186") (name "unconnected-(U1A-PA5-Pad15)") (class "Default")
      (node (ref "U1") (pin "15") (pinfunction "PA5_15") (pintype "bidirectional"))
    )
    (net (code "187") (name "unconnected-(U1A-PB0-Pad18)") (class "Default")
      (node (ref "U1") (pin "18") (pinfunction "PB0_18") (pintype "bidirectional"))
    )
    (net (code "188") (name "unconnected-(U1A-PB2-Pad20)") (class "Default")
      (node (ref "U1") (pin "20") (pinfunction "PB2_20") (pintype "bidirectional"))
    )
    (net (code "189") (name "unconnected-(U1A-PB8-Pad45)") (class "Default")
      (node (ref "U1") (pin "45") (pinfunction "PB8_45") (pintype "bidirectional"))
    )
    (net (code "190") (name "unconnected-(U1A-PB12-Pad25)") (class "Default")
      (node (ref "U1") (pin "25") (pinfunction "PB12_25") (pintype "bidirectional"))
    )
    (net (code "191") (name "unconnected-(U1A-PB13-Pad26)") (class "Default")
      (node (ref "U1") (pin "26") (pinfunction "PB13_26") (pintype "bidirectional"))
    )
    (net (code "192") (name "unconnected-(U1A-PC13-TAMPER-RTC-Pad2)") (class "Default")
      (node (ref "U1") (pin "2") (pinfunction "PC13-TAMPER-RTC_2") (pintype "bidirectional"))
    )
    (net (code "193") (name "unconnected-(U1A-PC14-OSC32_IN-Pad3)") (class "Default")
      (node (ref "U1") (pin "3") (pinfunction "PC14-OSC32_IN_3") (pintype "bidirectional"))
    )
    (net (code "194") (name "unconnected-(U1A-PC15-OSC32_OUT-Pad4)") (class "Default")
      (node (ref "U1") (pin "4") (pinfunction "PC15-OSC32_OUT_4") (pintype "bidirectional"))
    )
    (net (code "195") (name "unconnected-(U5-ADC-Pad2)") (class "Default")
      (node (ref "U5") (pin "2") (pinfunction "ADC_2") (pintype "passive"))
    )
    (net (code "196") (name "unconnected-(U5-EN-Pad3)") (class "Default")
      (node (ref "U5") (pin "3") (pinfunction "EN_3") (pintype "passive"))
    )
    (net (code "197") (name "unconnected-(U5-IO2-Pad11)") (class "Default")
      (node (ref "U5") (pin "11") (pinfunction "IO2_11") (pintype "passive"))
    )
    (net (code "198") (name "unconnected-(U5-IO4-Pad13)") (class "Default")
      (node (ref "U5") (pin "13") (pinfunction "IO4_13") (pintype "passive"))
    )
    (net (code "199") (name "unconnected-(U5-IO5-Pad14)") (class "Default")
      (node (ref "U5") (pin "14") (pinfunction "IO5_14") (pintype "passive"))
    )
    (net (code "200") (name "unconnected-(U5-IO12-Pad6)") (class "Default")
      (node (ref "U5") (pin "6") (pinfunction "IO12_6") (pintype "passive"))
    )
    (net (code "201") (name "unconnected-(U5-IO13-Pad7)") (class "Default")
      (node (ref "U5") (pin "7") (pinfunction "IO13_7") (pintype "passive"))
    )
    (net (code "202") (name "unconnected-(U5-IO14-Pad5)") (class "Default")
      (node (ref "U5") (pin "5") (pinfunction "IO14_5") (pintype "passive"))
    )
    (net (code "203") (name "unconnected-(U5-IO15-Pad10)") (class "Default")
      (node (ref "U5") (pin "10") (pinfunction "IO15_10") (pintype "passive"))
    )
    (net (code "204") (name "unconnected-(U5-IO16-Pad4)") (class "Default")
      (node (ref "U5") (pin "4") (pinfunction "IO16_4") (pintype "passive"))
    )
    (net (code "205") (name "unconnected-(U5-RST-Pad1)") (class "Default")
      (node (ref "U5") (pin "1") (pinfunction "RST_1") (pintype "passive"))
    )
    (net (code "206") (name "unconnected-(U12-DO-Pad2)") (class "Default")
      (node (ref "U12") (pin "2") (pinfunction "DO_2") (pintype "passive"))
    )
    (net (code "207") (name "unconnected-(U15-DO-Pad5)") (class "Default")
      (node (ref "U15") (pin "5") (pinfunction "DO_5") (pintype "passive"))
    )
    (net (code "208") (name "unconnected-(U16-CTS#-Pad9)") (class "Default")
      (node (ref "U16") (pin "9") (pinfunction "CTS#_9") (pintype "passive"))
    )
    (net (code "209") (name "unconnected-(U16-DCD#-Pad13)") (class "Default")
      (node (ref "U16") (pin "13") (pinfunction "DCD#_13") (pintype "passive"))
    )
    (net (code "210") (name "unconnected-(U16-DSR#-Pad10)") (class "Default")
      (node (ref "U16") (pin "10") (pinfunction "DSR#_10") (pintype "passive"))
    )
    (net (code "211") (name "unconnected-(U16-DTR#-Pad12)") (class "Default")
      (node (ref "U16") (pin "12") (pinfunction "DTR#_12") (pintype "passive"))
    )
    (net (code "212") (name "unconnected-(U16-R232-Pad15)") (class "Default")
      (node (ref "U16") (pin "15") (pinfunction "R232_15") (pintype "passive"))
    )
    (net (code "213") (name "unconnected-(U16-RI#-Pad14)") (class "Default")
      (node (ref "U16") (pin "14") (pinfunction "RI#_14") (pintype "passive"))
    )
    (net (code "214") (name "unconnected-(U16-RTS#-Pad11)") (class "Default")
      (node (ref "U16") (pin "11") (pinfunction "RTS#_11") (pintype "passive"))
    )
    (net (code "215") (name "unconnected-(U16-XI-Pad7)") (class "Default")
      (node (ref "U16") (pin "7") (pinfunction "XI_7") (pintype "passive"))
    )
    (net (code "216") (name "unconnected-(U16-XO-Pad8)") (class "Default")
      (node (ref "U16") (pin "8") (pinfunction "XO_8") (pintype "passive"))
    )
    (net (code "217") (name "unconnected-(U22-QH'-Pad9)") (class "Default")
      (node (ref "U22") (pin "9") (pinfunction "QH'_9") (pintype "output"))
    )
    (net (code "218") (name "unconnected-(U29-32KHZ-Pad1)") (class "Default")
      (node (ref "U29") (pin "1") (pinfunction "32KHZ_1") (pintype "passive"))
    )
    (net (code "219") (name "unconnected-(U29-~{RST}-Pad4)") (class "Default")
      (node (ref "U29") (pin "4") (pinfunction "~{RST}_4") (pintype "passive"))
    )
  )
)
